# ram-2mb.net
KiCad netlist of a schematic drawn in EAGLE
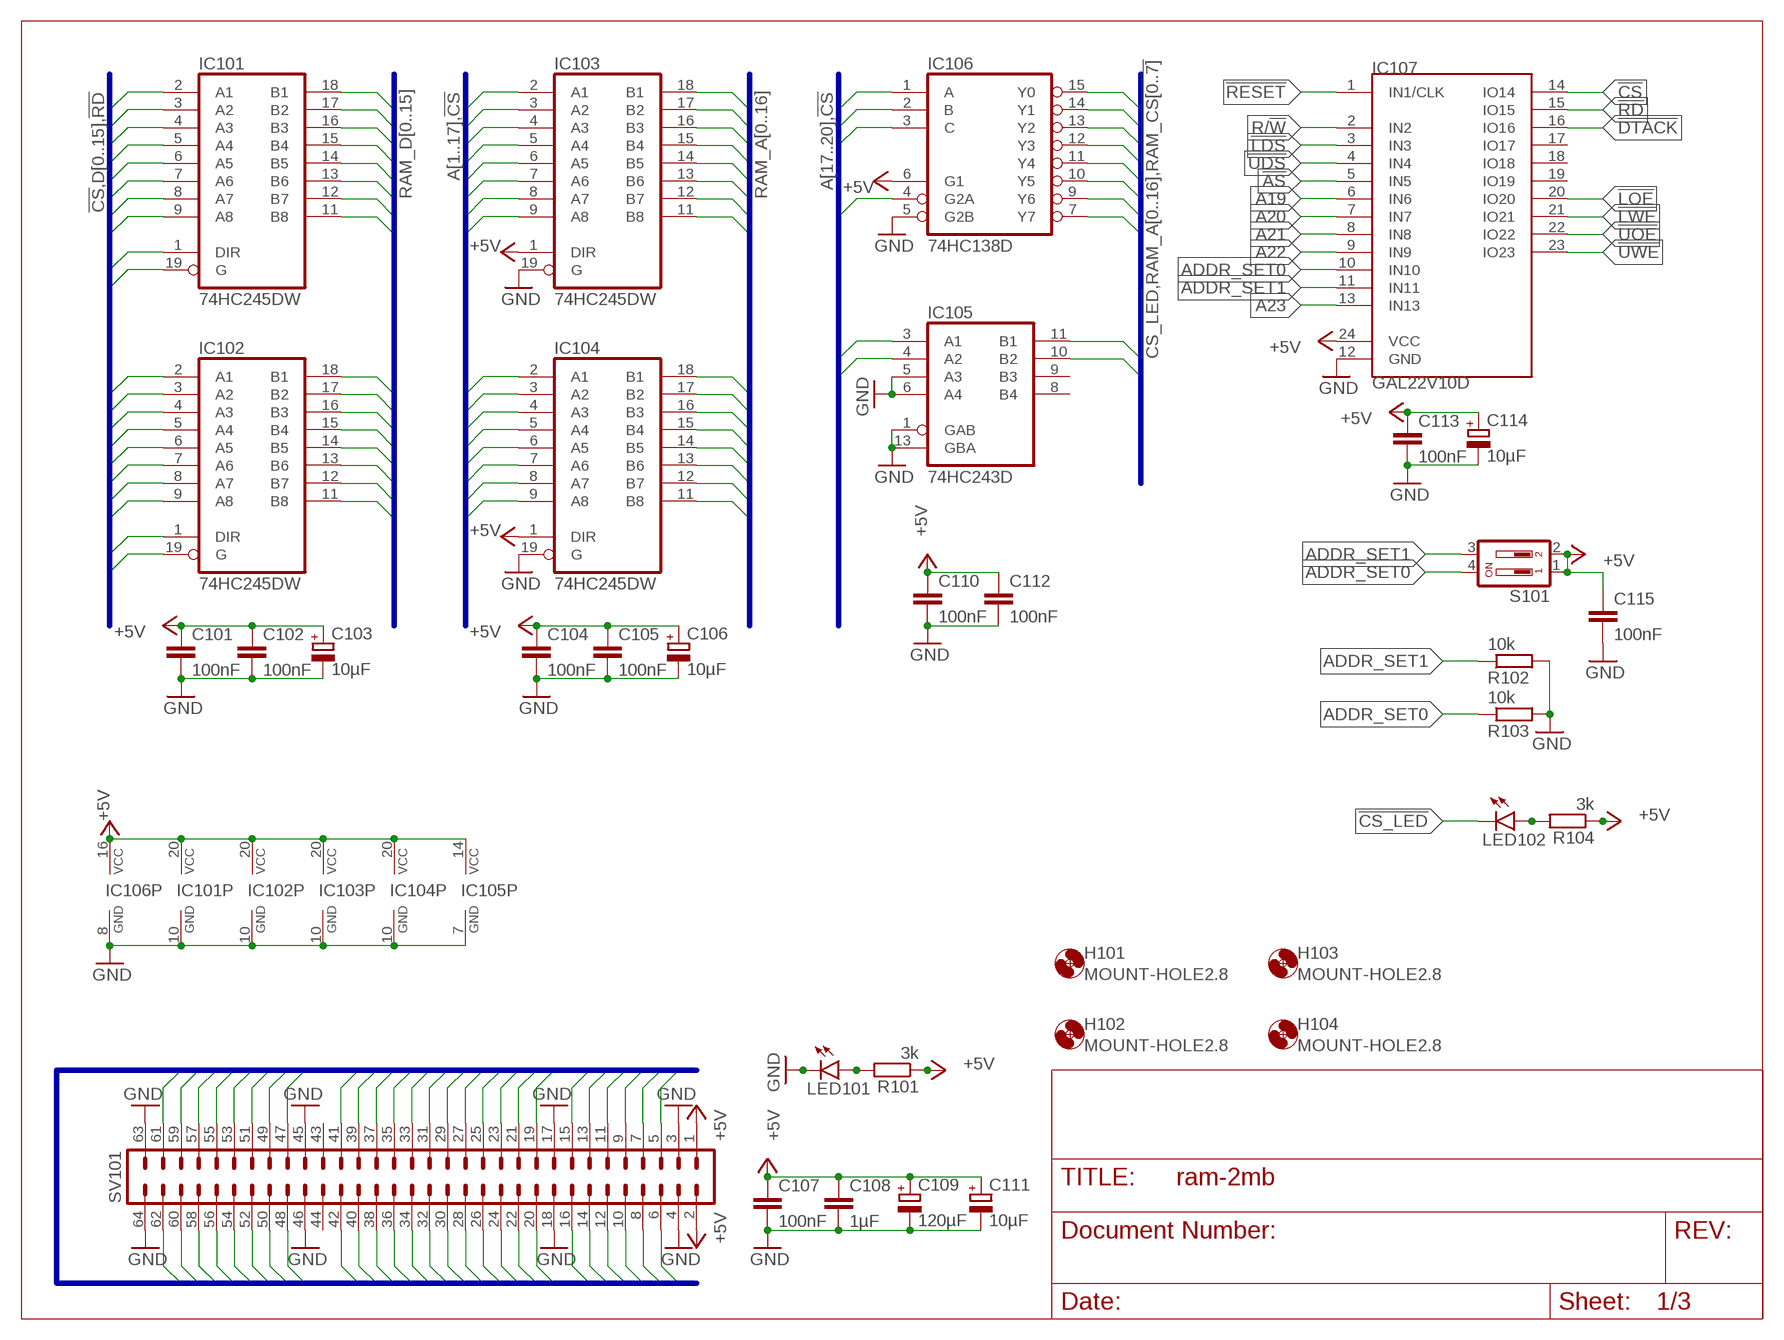
[diagram p0: schematic, sheet 1]
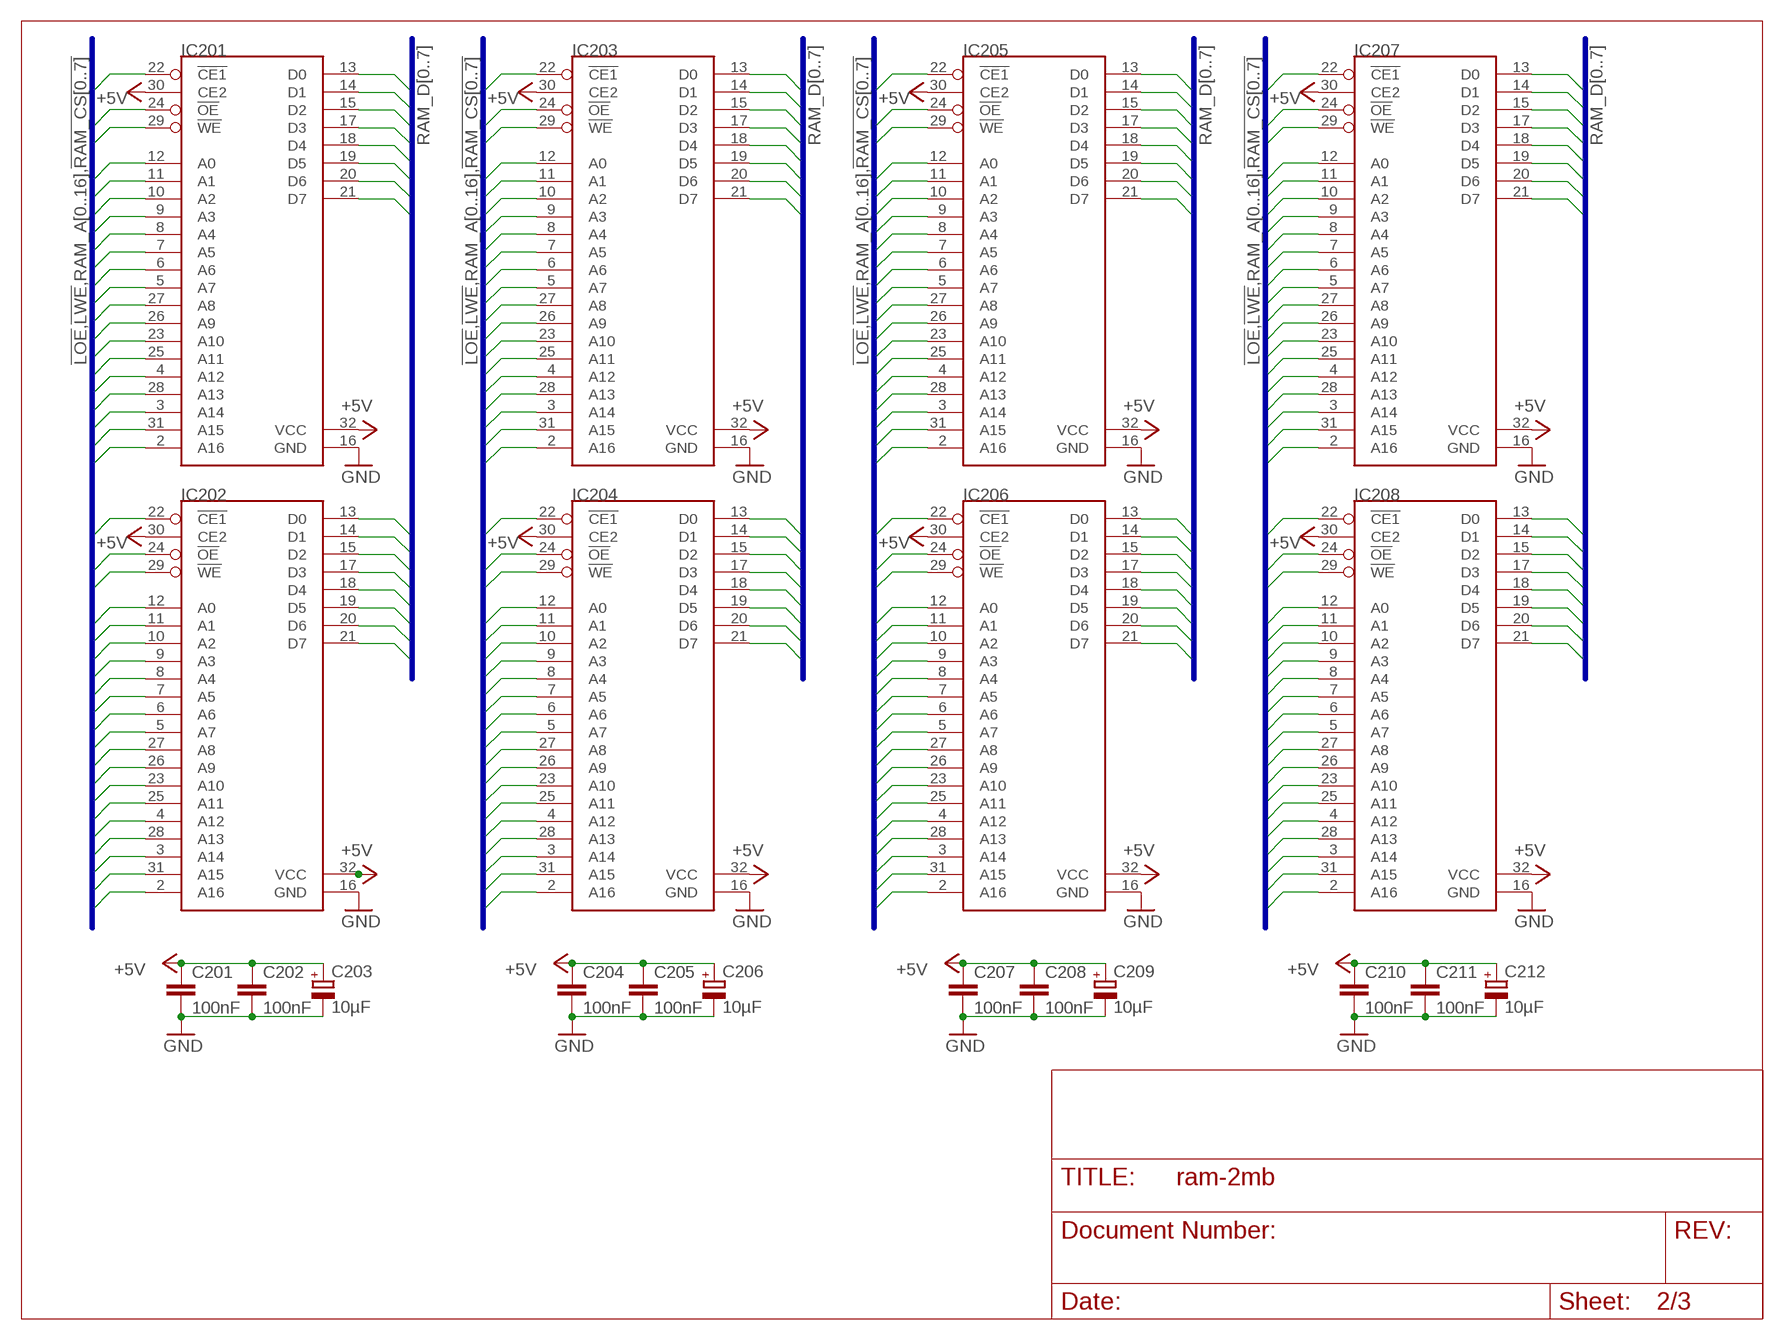
[diagram p1: schematic, sheet 2]
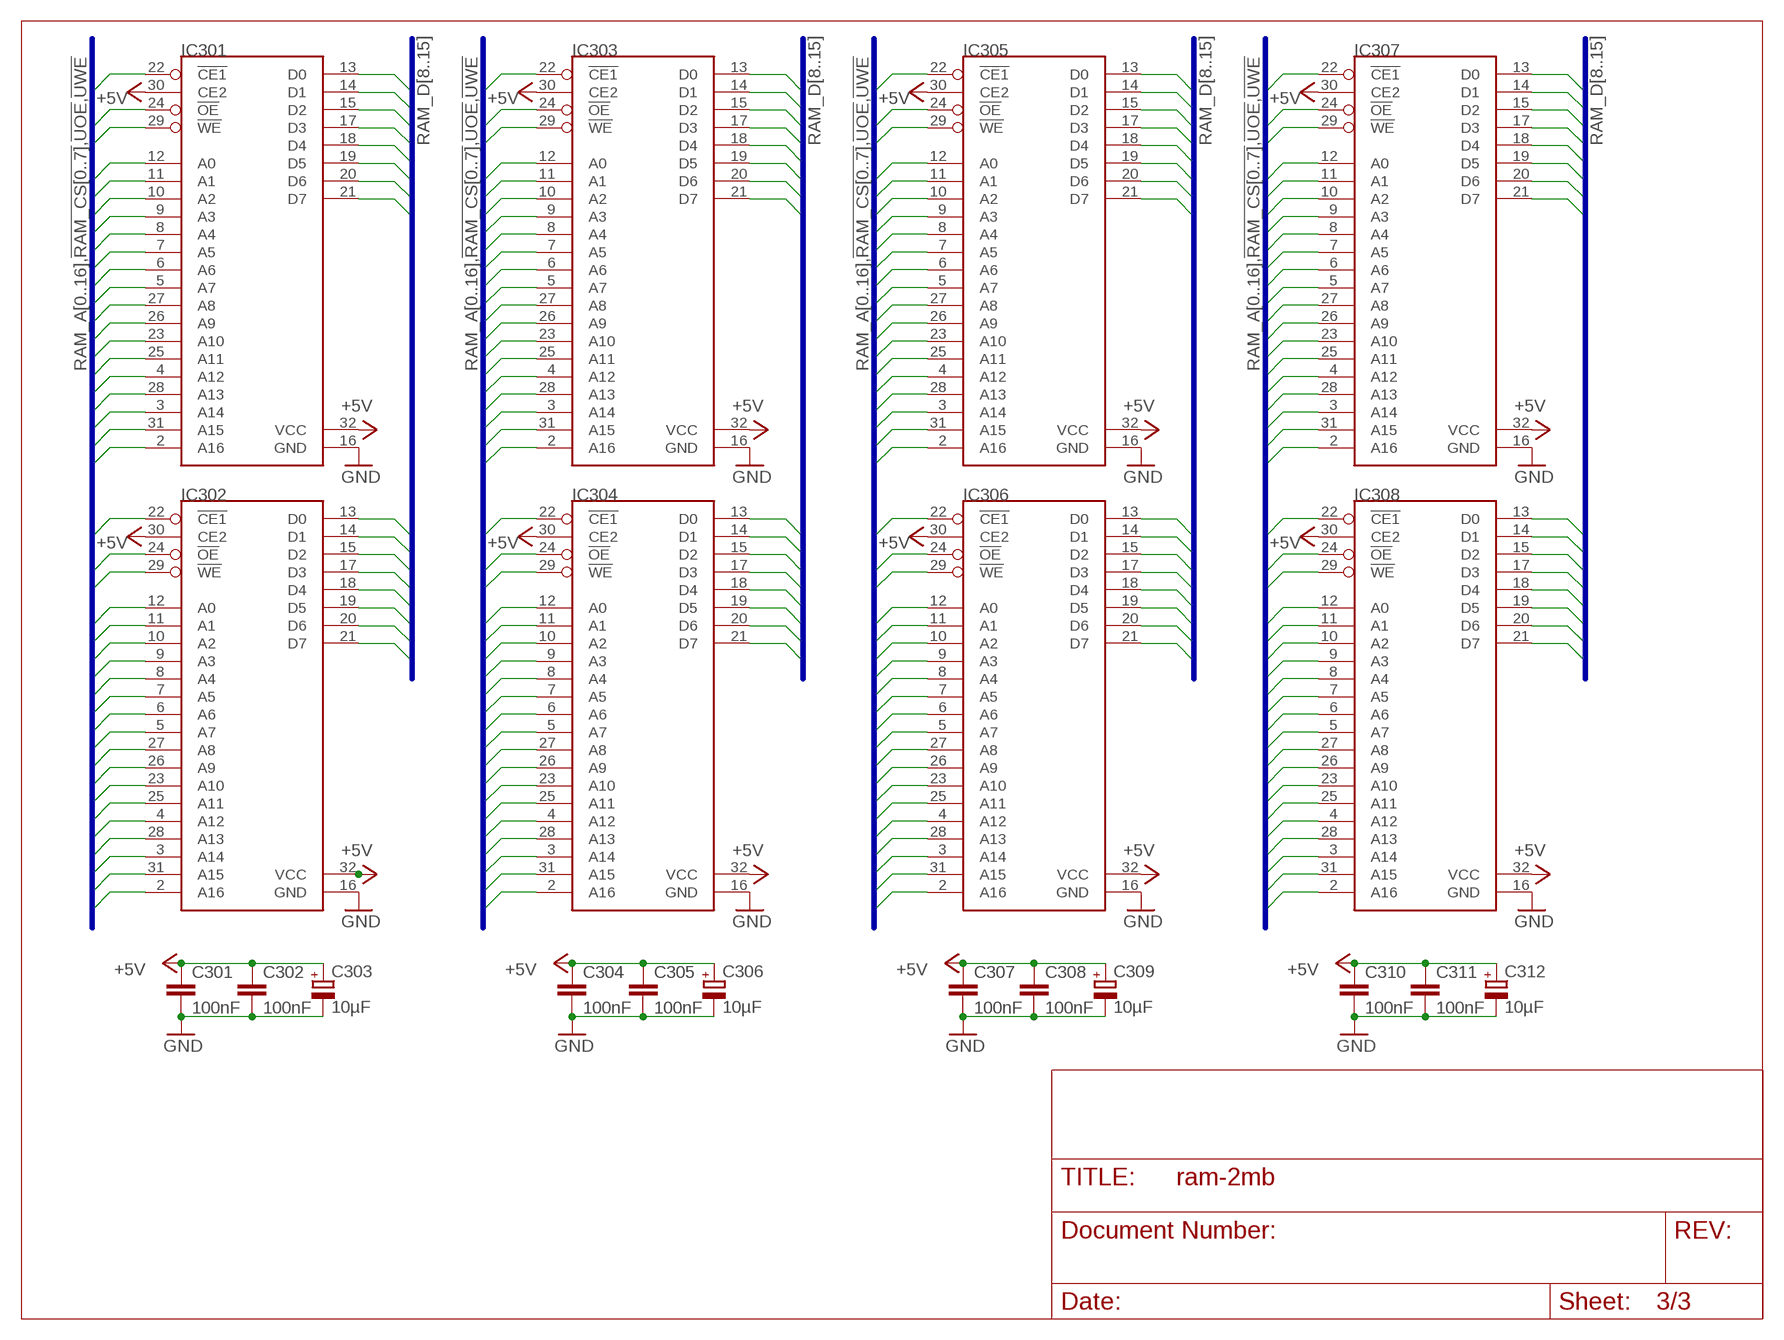
[diagram p2: schematic, sheet 3]

(export (version "E")
  (design (tool "Eeschema 10.0.6"))
  (components
    (comp (ref "C101")
      (value "100nF")
      (footprint "eagle-import:C0805")
      (libsource (lib "eagle-import") (part "C-EUC0805"))
    )
    (comp (ref "C102")
      (value "100nF")
      (footprint "eagle-import:C0805")
      (libsource (lib "eagle-import") (part "C-EUC0805"))
    )
    (comp (ref "C103")
      (value "10µF")
      (footprint "eagle-import:SMC_B")
      (libsource (lib "eagle-import") (part "CPOL-EUSMCB"))
    )
    (comp (ref "C104")
      (value "100nF")
      (footprint "eagle-import:C0805")
      (libsource (lib "eagle-import") (part "C-EUC0805"))
    )
    (comp (ref "C105")
      (value "100nF")
      (footprint "eagle-import:C0805")
      (libsource (lib "eagle-import") (part "C-EUC0805"))
    )
    (comp (ref "C106")
      (value "10µF")
      (footprint "eagle-import:SMC_B")
      (libsource (lib "eagle-import") (part "CPOL-EUSMCB"))
    )
    (comp (ref "C107")
      (value "100nF")
      (footprint "eagle-import:C0805")
      (libsource (lib "eagle-import") (part "C-EUC0805"))
    )
    (comp (ref "C108")
      (value "1µF")
      (footprint "eagle-import:C0805")
      (libsource (lib "eagle-import") (part "C-EUC0805"))
    )
    (comp (ref "C109")
      (value "120µF")
      (footprint "eagle-import:E2,5-7")
      (libsource (lib "eagle-import") (part "CPOL-EUE2.5-7"))
    )
    (comp (ref "C110")
      (value "100nF")
      (footprint "eagle-import:C0805")
      (libsource (lib "eagle-import") (part "C-EUC0805"))
    )
    (comp (ref "C111")
      (value "10µF")
      (footprint "eagle-import:SMC_B")
      (libsource (lib "eagle-import") (part "CPOL-EUSMCB"))
    )
    (comp (ref "C112")
      (value "100nF")
      (footprint "eagle-import:C0805")
      (libsource (lib "eagle-import") (part "C-EUC0805"))
    )
    (comp (ref "C113")
      (value "100nF")
      (footprint "eagle-import:C0805")
      (libsource (lib "eagle-import") (part "C-EUC0805"))
    )
    (comp (ref "C114")
      (value "10µF")
      (footprint "eagle-import:SMC_B")
      (libsource (lib "eagle-import") (part "CPOL-EUSMCB"))
    )
    (comp (ref "C115")
      (value "100nF")
      (footprint "eagle-import:C0805")
      (libsource (lib "eagle-import") (part "C-EUC0805"))
    )
    (comp (ref "H101")
      (value "MOUNT-HOLE2.8")
      (footprint "eagle-import:2,8")
      (libsource (lib "eagle-import") (part "MOUNT-HOLE2.8"))
    )
    (comp (ref "H102")
      (value "MOUNT-HOLE2.8")
      (footprint "eagle-import:2,8")
      (libsource (lib "eagle-import") (part "MOUNT-HOLE2.8"))
    )
    (comp (ref "H103")
      (value "MOUNT-HOLE2.8")
      (footprint "eagle-import:2,8")
      (libsource (lib "eagle-import") (part "MOUNT-HOLE2.8"))
    )
    (comp (ref "H104")
      (value "MOUNT-HOLE2.8")
      (footprint "eagle-import:2,8")
      (libsource (lib "eagle-import") (part "MOUNT-HOLE2.8"))
    )
    (comp (ref "IC101")
      (value "74HC245DW")
      (footprint "eagle-import:SO20W")
      (fields (field (name "MOUSER") "595-SN74HC245DWR"))
      (libsource (lib "eagle-import") (part "74245DWHC"))
    )
    (comp (ref "IC102")
      (value "74HC245DW")
      (footprint "eagle-import:SO20W")
      (fields (field (name "MOUSER") "595-SN74HC245DWR"))
      (libsource (lib "eagle-import") (part "74245DWHC"))
    )
    (comp (ref "IC103")
      (value "74HC245DW")
      (footprint "eagle-import:SO20W")
      (fields (field (name "MOUSER") "595-SN74HC245DWR"))
      (libsource (lib "eagle-import") (part "74245DWHC"))
    )
    (comp (ref "IC104")
      (value "74HC245DW")
      (footprint "eagle-import:SO20W")
      (fields (field (name "MOUSER") "595-SN74HC245DWR"))
      (libsource (lib "eagle-import") (part "74245DWHC"))
    )
    (comp (ref "IC105")
      (value "74HC243D")
      (footprint "eagle-import:SO14")
      (fields (field (name "MOUSER") "595-CD74HC243M96"))
      (libsource (lib "eagle-import") (part "74243DHC"))
    )
    (comp (ref "IC106")
      (value "74HC138D")
      (footprint "eagle-import:SO16")
      (fields (field (name "MOUSER") "595-SN74HC138DG4"))
      (libsource (lib "eagle-import") (part "74138DHC"))
    )
    (comp (ref "IC107")
      (value "GAL22V10D")
      (footprint "eagle-import:DIL24S")
      (libsource (lib "eagle-import") (part "GAL22V10DIP24"))
    )
    (comp (ref "LED101")
      (value "LEDCHIPLED_1206")
      (footprint "eagle-import:CHIPLED_1206")
      (libsource (lib "eagle-import") (part "LEDCHIPLED_1206"))
    )
    (comp (ref "LED102")
      (value "LEDCHIPLED_1206")
      (footprint "eagle-import:CHIPLED_1206")
      (libsource (lib "eagle-import") (part "LEDCHIPLED_1206"))
    )
    (comp (ref "R101")
      (value "3k")
      (footprint "eagle-import:R2012")
      (libsource (lib "eagle-import") (part "R-EU_R2012"))
    )
    (comp (ref "R102")
      (value "10k")
      (footprint "eagle-import:R2012")
      (libsource (lib "eagle-import") (part "R-EU_R2012"))
    )
    (comp (ref "R103")
      (value "10k")
      (footprint "eagle-import:R2012")
      (libsource (lib "eagle-import") (part "R-EU_R2012"))
    )
    (comp (ref "R104")
      (value "3k")
      (footprint "eagle-import:R2012")
      (libsource (lib "eagle-import") (part "R-EU_R2012"))
    )
    (comp (ref "S101")
      (value "DP02")
      (footprint "eagle-import:DP-02")
      (fields (field (name "MPN") "MCDP02"))
      (libsource (lib "eagle-import") (part "DP02"))
    )
    (comp (ref "SV101")
      (value "ML64L")
      (footprint "eagle-import:ML64L")
      (libsource (lib "eagle-import") (part "ML64L"))
    )
    (comp (ref "C301")
      (value "100nF")
      (footprint "eagle-import:C0805")
      (libsource (lib "eagle-import") (part "C-EUC0805"))
    )
    (comp (ref "C302")
      (value "100nF")
      (footprint "eagle-import:C0805")
      (libsource (lib "eagle-import") (part "C-EUC0805"))
    )
    (comp (ref "C303")
      (value "10µF")
      (footprint "eagle-import:SMC_B")
      (libsource (lib "eagle-import") (part "CPOL-EUSMCB"))
    )
    (comp (ref "C304")
      (value "100nF")
      (footprint "eagle-import:C0805")
      (libsource (lib "eagle-import") (part "C-EUC0805"))
    )
    (comp (ref "C305")
      (value "100nF")
      (footprint "eagle-import:C0805")
      (libsource (lib "eagle-import") (part "C-EUC0805"))
    )
    (comp (ref "C306")
      (value "10µF")
      (footprint "eagle-import:SMC_B")
      (libsource (lib "eagle-import") (part "CPOL-EUSMCB"))
    )
    (comp (ref "C307")
      (value "100nF")
      (footprint "eagle-import:C0805")
      (libsource (lib "eagle-import") (part "C-EUC0805"))
    )
    (comp (ref "C308")
      (value "100nF")
      (footprint "eagle-import:C0805")
      (libsource (lib "eagle-import") (part "C-EUC0805"))
    )
    (comp (ref "C309")
      (value "10µF")
      (footprint "eagle-import:SMC_B")
      (libsource (lib "eagle-import") (part "CPOL-EUSMCB"))
    )
    (comp (ref "C310")
      (value "100nF")
      (footprint "eagle-import:C0805")
      (libsource (lib "eagle-import") (part "C-EUC0805"))
    )
    (comp (ref "C311")
      (value "100nF")
      (footprint "eagle-import:C0805")
      (libsource (lib "eagle-import") (part "C-EUC0805"))
    )
    (comp (ref "C312")
      (value "10µF")
      (footprint "eagle-import:SMC_B")
      (libsource (lib "eagle-import") (part "CPOL-EUSMCB"))
    )
    (comp (ref "IC301")
      (value "CY62128BSOIC32-450")
      (footprint "eagle-import:SOIC127P1412X299-32N")
      (libsource (lib "eagle-import") (part "CY62128BSOIC32-450"))
    )
    (comp (ref "IC302")
      (value "CY62128BSOIC32-450")
      (footprint "eagle-import:SOIC127P1412X299-32N")
      (libsource (lib "eagle-import") (part "CY62128BSOIC32-450"))
    )
    (comp (ref "IC303")
      (value "CY62128BSOIC32-450")
      (footprint "eagle-import:SOIC127P1412X299-32N")
      (libsource (lib "eagle-import") (part "CY62128BSOIC32-450"))
    )
    (comp (ref "IC304")
      (value "CY62128BSOIC32-450")
      (footprint "eagle-import:SOIC127P1412X299-32N")
      (libsource (lib "eagle-import") (part "CY62128BSOIC32-450"))
    )
    (comp (ref "IC305")
      (value "CY62128BSOIC32-450")
      (footprint "eagle-import:SOIC127P1412X299-32N")
      (libsource (lib "eagle-import") (part "CY62128BSOIC32-450"))
    )
    (comp (ref "IC306")
      (value "CY62128BSOIC32-450")
      (footprint "eagle-import:SOIC127P1412X299-32N")
      (libsource (lib "eagle-import") (part "CY62128BSOIC32-450"))
    )
    (comp (ref "IC307")
      (value "CY62128BSOIC32-450")
      (footprint "eagle-import:SOIC127P1412X299-32N")
      (libsource (lib "eagle-import") (part "CY62128BSOIC32-450"))
    )
    (comp (ref "IC308")
      (value "CY62128BSOIC32-450")
      (footprint "eagle-import:SOIC127P1412X299-32N")
      (libsource (lib "eagle-import") (part "CY62128BSOIC32-450"))
    )
    (comp (ref "C201")
      (value "100nF")
      (footprint "eagle-import:C0805")
      (libsource (lib "eagle-import") (part "C-EUC0805"))
    )
    (comp (ref "C202")
      (value "100nF")
      (footprint "eagle-import:C0805")
      (libsource (lib "eagle-import") (part "C-EUC0805"))
    )
    (comp (ref "C203")
      (value "10µF")
      (footprint "eagle-import:SMC_B")
      (libsource (lib "eagle-import") (part "CPOL-EUSMCB"))
    )
    (comp (ref "C204")
      (value "100nF")
      (footprint "eagle-import:C0805")
      (libsource (lib "eagle-import") (part "C-EUC0805"))
    )
    (comp (ref "C205")
      (value "100nF")
      (footprint "eagle-import:C0805")
      (libsource (lib "eagle-import") (part "C-EUC0805"))
    )
    (comp (ref "C206")
      (value "10µF")
      (footprint "eagle-import:SMC_B")
      (libsource (lib "eagle-import") (part "CPOL-EUSMCB"))
    )
    (comp (ref "C207")
      (value "100nF")
      (footprint "eagle-import:C0805")
      (libsource (lib "eagle-import") (part "C-EUC0805"))
    )
    (comp (ref "C208")
      (value "100nF")
      (footprint "eagle-import:C0805")
      (libsource (lib "eagle-import") (part "C-EUC0805"))
    )
    (comp (ref "C209")
      (value "10µF")
      (footprint "eagle-import:SMC_B")
      (libsource (lib "eagle-import") (part "CPOL-EUSMCB"))
    )
    (comp (ref "C210")
      (value "100nF")
      (footprint "eagle-import:C0805")
      (libsource (lib "eagle-import") (part "C-EUC0805"))
    )
    (comp (ref "C211")
      (value "100nF")
      (footprint "eagle-import:C0805")
      (libsource (lib "eagle-import") (part "C-EUC0805"))
    )
    (comp (ref "C212")
      (value "10µF")
      (footprint "eagle-import:SMC_B")
      (libsource (lib "eagle-import") (part "CPOL-EUSMCB"))
    )
    (comp (ref "IC201")
      (value "CY62128BSOIC32-450")
      (footprint "eagle-import:SOIC127P1412X299-32N")
      (libsource (lib "eagle-import") (part "CY62128BSOIC32-450"))
    )
    (comp (ref "IC202")
      (value "CY62128BSOIC32-450")
      (footprint "eagle-import:SOIC127P1412X299-32N")
      (libsource (lib "eagle-import") (part "CY62128BSOIC32-450"))
    )
    (comp (ref "IC203")
      (value "CY62128BSOIC32-450")
      (footprint "eagle-import:SOIC127P1412X299-32N")
      (libsource (lib "eagle-import") (part "CY62128BSOIC32-450"))
    )
    (comp (ref "IC204")
      (value "CY62128BSOIC32-450")
      (footprint "eagle-import:SOIC127P1412X299-32N")
      (libsource (lib "eagle-import") (part "CY62128BSOIC32-450"))
    )
    (comp (ref "IC205")
      (value "CY62128BSOIC32-450")
      (footprint "eagle-import:SOIC127P1412X299-32N")
      (libsource (lib "eagle-import") (part "CY62128BSOIC32-450"))
    )
    (comp (ref "IC206")
      (value "CY62128BSOIC32-450")
      (footprint "eagle-import:SOIC127P1412X299-32N")
      (libsource (lib "eagle-import") (part "CY62128BSOIC32-450"))
    )
    (comp (ref "IC207")
      (value "CY62128BSOIC32-450")
      (footprint "eagle-import:SOIC127P1412X299-32N")
      (libsource (lib "eagle-import") (part "CY62128BSOIC32-450"))
    )
    (comp (ref "IC208")
      (value "CY62128BSOIC32-450")
      (footprint "eagle-import:SOIC127P1412X299-32N")
      (libsource (lib "eagle-import") (part "CY62128BSOIC32-450"))
    )
  )
  (nets
    (net (code "1") (name "+5V") (class "Default")
      (node (ref "C101") (pin "1") (pinfunction "1_1") (pintype "passive"))
      (node (ref "C102") (pin "1") (pinfunction "1_1") (pintype "passive"))
      (node (ref "C103") (pin "+") (pinfunction "+_+") (pintype "passive"))
      (node (ref "C104") (pin "1") (pinfunction "1_1") (pintype "passive"))
      (node (ref "C105") (pin "1") (pinfunction "1_1") (pintype "passive"))
      (node (ref "C106") (pin "+") (pinfunction "+_+") (pintype "passive"))
      (node (ref "C107") (pin "1") (pinfunction "1_1") (pintype "passive"))
      (node (ref "C108") (pin "1") (pinfunction "1_1") (pintype "passive"))
      (node (ref "C109") (pin "+") (pinfunction "+_+") (pintype "passive"))
      (node (ref "C110") (pin "1") (pinfunction "1_1") (pintype "passive"))
      (node (ref "C111") (pin "+") (pinfunction "+_+") (pintype "passive"))
      (node (ref "C112") (pin "1") (pinfunction "1_1") (pintype "passive"))
      (node (ref "C113") (pin "1") (pinfunction "1_1") (pintype "passive"))
      (node (ref "C114") (pin "+") (pinfunction "+_+") (pintype "passive"))
      (node (ref "C115") (pin "1") (pinfunction "1_1") (pintype "passive"))
      (node (ref "C201") (pin "1") (pinfunction "1_1") (pintype "passive"))
      (node (ref "C202") (pin "1") (pinfunction "1_1") (pintype "passive"))
      (node (ref "C203") (pin "+") (pinfunction "+_+") (pintype "passive"))
      (node (ref "C204") (pin "1") (pinfunction "1_1") (pintype "passive"))
      (node (ref "C205") (pin "1") (pinfunction "1_1") (pintype "passive"))
      (node (ref "C206") (pin "+") (pinfunction "+_+") (pintype "passive"))
      (node (ref "C207") (pin "1") (pinfunction "1_1") (pintype "passive"))
      (node (ref "C208") (pin "1") (pinfunction "1_1") (pintype "passive"))
      (node (ref "C209") (pin "+") (pinfunction "+_+") (pintype "passive"))
      (node (ref "C210") (pin "1") (pinfunction "1_1") (pintype "passive"))
      (node (ref "C211") (pin "1") (pinfunction "1_1") (pintype "passive"))
      (node (ref "C212") (pin "+") (pinfunction "+_+") (pintype "passive"))
      (node (ref "C301") (pin "1") (pinfunction "1_1") (pintype "passive"))
      (node (ref "C302") (pin "1") (pinfunction "1_1") (pintype "passive"))
      (node (ref "C303") (pin "+") (pinfunction "+_+") (pintype "passive"))
      (node (ref "C304") (pin "1") (pinfunction "1_1") (pintype "passive"))
      (node (ref "C305") (pin "1") (pinfunction "1_1") (pintype "passive"))
      (node (ref "C306") (pin "+") (pinfunction "+_+") (pintype "passive"))
      (node (ref "C307") (pin "1") (pinfunction "1_1") (pintype "passive"))
      (node (ref "C308") (pin "1") (pinfunction "1_1") (pintype "passive"))
      (node (ref "C309") (pin "+") (pinfunction "+_+") (pintype "passive"))
      (node (ref "C310") (pin "1") (pinfunction "1_1") (pintype "passive"))
      (node (ref "C311") (pin "1") (pinfunction "1_1") (pintype "passive"))
      (node (ref "C312") (pin "+") (pinfunction "+_+") (pintype "passive"))
      (node (ref "IC101") (pin "20") (pinfunction "VCC_20") (pintype "power_in"))
      (node (ref "IC102") (pin "20") (pinfunction "VCC_20") (pintype "power_in"))
      (node (ref "IC103") (pin "1") (pinfunction "DIR_1") (pintype "input"))
      (node (ref "IC103") (pin "20") (pinfunction "VCC_20") (pintype "power_in"))
      (node (ref "IC104") (pin "1") (pinfunction "DIR_1") (pintype "input"))
      (node (ref "IC104") (pin "20") (pinfunction "VCC_20") (pintype "power_in"))
      (node (ref "IC105") (pin "14") (pinfunction "VCC_14") (pintype "power_in"))
      (node (ref "IC106") (pin "16") (pinfunction "VCC_16") (pintype "power_in"))
      (node (ref "IC106") (pin "6") (pinfunction "G1_6") (pintype "input"))
      (node (ref "IC107") (pin "24") (pinfunction "VCC_24") (pintype "power_in"))
      (node (ref "IC201") (pin "30") (pinfunction "CE2_30") (pintype "input"))
      (node (ref "IC201") (pin "32") (pinfunction "VCC_32") (pintype "power_in"))
      (node (ref "IC202") (pin "30") (pinfunction "CE2_30") (pintype "input"))
      (node (ref "IC202") (pin "32") (pinfunction "VCC_32") (pintype "power_in"))
      (node (ref "IC203") (pin "30") (pinfunction "CE2_30") (pintype "input"))
      (node (ref "IC203") (pin "32") (pinfunction "VCC_32") (pintype "power_in"))
      (node (ref "IC204") (pin "30") (pinfunction "CE2_30") (pintype "input"))
      (node (ref "IC204") (pin "32") (pinfunction "VCC_32") (pintype "power_in"))
      (node (ref "IC205") (pin "30") (pinfunction "CE2_30") (pintype "input"))
      (node (ref "IC205") (pin "32") (pinfunction "VCC_32") (pintype "power_in"))
      (node (ref "IC206") (pin "30") (pinfunction "CE2_30") (pintype "input"))
      (node (ref "IC206") (pin "32") (pinfunction "VCC_32") (pintype "power_in"))
      (node (ref "IC207") (pin "30") (pinfunction "CE2_30") (pintype "input"))
      (node (ref "IC207") (pin "32") (pinfunction "VCC_32") (pintype "power_in"))
      (node (ref "IC208") (pin "30") (pinfunction "CE2_30") (pintype "input"))
      (node (ref "IC208") (pin "32") (pinfunction "VCC_32") (pintype "power_in"))
      (node (ref "IC301") (pin "30") (pinfunction "CE2_30") (pintype "input"))
      (node (ref "IC301") (pin "32") (pinfunction "VCC_32") (pintype "power_in"))
      (node (ref "IC302") (pin "30") (pinfunction "CE2_30") (pintype "input"))
      (node (ref "IC302") (pin "32") (pinfunction "VCC_32") (pintype "power_in"))
      (node (ref "IC303") (pin "30") (pinfunction "CE2_30") (pintype "input"))
      (node (ref "IC303") (pin "32") (pinfunction "VCC_32") (pintype "power_in"))
      (node (ref "IC304") (pin "30") (pinfunction "CE2_30") (pintype "input"))
      (node (ref "IC304") (pin "32") (pinfunction "VCC_32") (pintype "power_in"))
      (node (ref "IC305") (pin "30") (pinfunction "CE2_30") (pintype "input"))
      (node (ref "IC305") (pin "32") (pinfunction "VCC_32") (pintype "power_in"))
      (node (ref "IC306") (pin "30") (pinfunction "CE2_30") (pintype "input"))
      (node (ref "IC306") (pin "32") (pinfunction "VCC_32") (pintype "power_in"))
      (node (ref "IC307") (pin "30") (pinfunction "CE2_30") (pintype "input"))
      (node (ref "IC307") (pin "32") (pinfunction "VCC_32") (pintype "power_in"))
      (node (ref "IC308") (pin "30") (pinfunction "CE2_30") (pintype "input"))
      (node (ref "IC308") (pin "32") (pinfunction "VCC_32") (pintype "power_in"))
      (node (ref "R101") (pin "1") (pinfunction "1_1") (pintype "passive"))
      (node (ref "R104") (pin "1") (pinfunction "1_1") (pintype "passive"))
      (node (ref "S101") (pin "1") (pinfunction "1_1") (pintype "passive"))
      (node (ref "S101") (pin "2") (pinfunction "2_2") (pintype "passive"))
      (node (ref "SV101") (pin "1") (pinfunction "1_1") (pintype "passive"))
      (node (ref "SV101") (pin "2") (pinfunction "2_2") (pintype "passive"))
    )
    (net (code "12") (name "A1") (class "Default")
      (node (ref "IC103") (pin "2") (pinfunction "A1_2") (pintype "bidirectional"))
      (node (ref "SV101") (pin "20") (pinfunction "20_20") (pintype "passive"))
    )
    (net (code "13") (name "A2") (class "Default")
      (node (ref "IC103") (pin "3") (pinfunction "A2_3") (pintype "bidirectional"))
      (node (ref "SV101") (pin "22") (pinfunction "22_22") (pintype "passive"))
    )
    (net (code "14") (name "A3") (class "Default")
      (node (ref "IC103") (pin "4") (pinfunction "A3_4") (pintype "bidirectional"))
      (node (ref "SV101") (pin "19") (pinfunction "19_19") (pintype "passive"))
    )
    (net (code "15") (name "A4") (class "Default")
      (node (ref "IC103") (pin "5") (pinfunction "A4_5") (pintype "bidirectional"))
      (node (ref "SV101") (pin "24") (pinfunction "24_24") (pintype "passive"))
    )
    (net (code "16") (name "A5") (class "Default")
      (node (ref "IC103") (pin "6") (pinfunction "A5_6") (pintype "bidirectional"))
      (node (ref "SV101") (pin "21") (pinfunction "21_21") (pintype "passive"))
    )
    (net (code "17") (name "A6") (class "Default")
      (node (ref "IC103") (pin "7") (pinfunction "A6_7") (pintype "bidirectional"))
      (node (ref "SV101") (pin "23") (pinfunction "23_23") (pintype "passive"))
    )
    (net (code "18") (name "A7") (class "Default")
      (node (ref "IC103") (pin "8") (pinfunction "A7_8") (pintype "bidirectional"))
      (node (ref "SV101") (pin "26") (pinfunction "26_26") (pintype "passive"))
    )
    (net (code "19") (name "A8") (class "Default")
      (node (ref "IC103") (pin "9") (pinfunction "A8_9") (pintype "bidirectional"))
      (node (ref "SV101") (pin "25") (pinfunction "25_25") (pintype "passive"))
    )
    (net (code "20") (name "A9") (class "Default")
      (node (ref "IC104") (pin "2") (pinfunction "A1_2") (pintype "bidirectional"))
      (node (ref "SV101") (pin "28") (pinfunction "28_28") (pintype "passive"))
    )
    (net (code "21") (name "A10") (class "Default")
      (node (ref "IC104") (pin "3") (pinfunction "A2_3") (pintype "bidirectional"))
      (node (ref "SV101") (pin "27") (pinfunction "27_27") (pintype "passive"))
    )
    (net (code "22") (name "A11") (class "Default")
      (node (ref "IC104") (pin "4") (pinfunction "A3_4") (pintype "bidirectional"))
      (node (ref "SV101") (pin "30") (pinfunction "30_30") (pintype "passive"))
    )
    (net (code "23") (name "A12") (class "Default")
      (node (ref "IC104") (pin "5") (pinfunction "A4_5") (pintype "bidirectional"))
      (node (ref "SV101") (pin "29") (pinfunction "29_29") (pintype "passive"))
    )
    (net (code "24") (name "A13") (class "Default")
      (node (ref "IC104") (pin "6") (pinfunction "A5_6") (pintype "bidirectional"))
      (node (ref "SV101") (pin "31") (pinfunction "31_31") (pintype "passive"))
    )
    (net (code "25") (name "A14") (class "Default")
      (node (ref "IC104") (pin "7") (pinfunction "A6_7") (pintype "bidirectional"))
      (node (ref "SV101") (pin "32") (pinfunction "32_32") (pintype "passive"))
    )
    (net (code "26") (name "A15") (class "Default")
      (node (ref "IC104") (pin "8") (pinfunction "A7_8") (pintype "bidirectional"))
      (node (ref "SV101") (pin "33") (pinfunction "33_33") (pintype "passive"))
    )
    (net (code "27") (name "A16") (class "Default")
      (node (ref "IC104") (pin "9") (pinfunction "A8_9") (pintype "bidirectional"))
      (node (ref "SV101") (pin "34") (pinfunction "34_34") (pintype "passive"))
    )
    (net (code "28") (name "A17") (class "Default")
      (node (ref "IC105") (pin "3") (pinfunction "A1_3") (pintype "bidirectional"))
      (node (ref "SV101") (pin "36") (pinfunction "36_36") (pintype "passive"))
    )
    (net (code "29") (name "A18") (class "Default")
      (node (ref "IC106") (pin "1") (pinfunction "A_1") (pintype "input"))
      (node (ref "SV101") (pin "35") (pinfunction "35_35") (pintype "passive"))
    )
    (net (code "30") (name "A19") (class "Default")
      (node (ref "IC106") (pin "2") (pinfunction "B_2") (pintype "input"))
      (node (ref "IC107") (pin "6") (pinfunction "IN6_6") (pintype "input"))
      (node (ref "SV101") (pin "38") (pinfunction "38_38") (pintype "passive"))
    )
    (net (code "31") (name "A20") (class "Default")
      (node (ref "IC106") (pin "3") (pinfunction "C_3") (pintype "input"))
      (node (ref "IC107") (pin "7") (pinfunction "IN7_7") (pintype "input"))
      (node (ref "SV101") (pin "37") (pinfunction "37_37") (pintype "passive"))
    )
    (net (code "32") (name "A21") (class "Default")
      (node (ref "IC107") (pin "8") (pinfunction "IN8_8") (pintype "input"))
      (node (ref "SV101") (pin "40") (pinfunction "40_40") (pintype "passive"))
    )
    (net (code "33") (name "A22") (class "Default")
      (node (ref "IC107") (pin "9") (pinfunction "IN9_9") (pintype "input"))
      (node (ref "SV101") (pin "39") (pinfunction "39_39") (pintype "passive"))
    )
    (net (code "34") (name "A23") (class "Default")
      (node (ref "IC107") (pin "13") (pinfunction "IN13_13") (pintype "input"))
      (node (ref "SV101") (pin "42") (pinfunction "42_42") (pintype "passive"))
    )
    (net (code "35") (name "ADDR_SET0") (class "Default")
      (node (ref "IC107") (pin "10") (pinfunction "IN10_10") (pintype "input"))
      (node (ref "R103") (pin "1") (pinfunction "1_1") (pintype "passive"))
      (node (ref "S101") (pin "4") (pinfunction "4_4") (pintype "passive"))
    )
    (net (code "36") (name "ADDR_SET1") (class "Default")
      (node (ref "IC107") (pin "11") (pinfunction "IN11_11") (pintype "input"))
      (node (ref "R102") (pin "1") (pinfunction "1_1") (pintype "passive"))
      (node (ref "S101") (pin "3") (pinfunction "3_3") (pintype "passive"))
    )
    (net (code "37") (name "D0") (class "Default")
      (node (ref "IC101") (pin "2") (pinfunction "A1_2") (pintype "bidirectional"))
      (node (ref "SV101") (pin "62") (pinfunction "62_62") (pintype "passive"))
    )
    (net (code "38") (name "D1") (class "Default")
      (node (ref "IC101") (pin "3") (pinfunction "A2_3") (pintype "bidirectional"))
      (node (ref "SV101") (pin "60") (pinfunction "60_60") (pintype "passive"))
    )
    (net (code "39") (name "D2") (class "Default")
      (node (ref "IC101") (pin "4") (pinfunction "A3_4") (pintype "bidirectional"))
      (node (ref "SV101") (pin "58") (pinfunction "58_58") (pintype "passive"))
    )
    (net (code "40") (name "D3") (class "Default")
      (node (ref "IC101") (pin "5") (pinfunction "A4_5") (pintype "bidirectional"))
      (node (ref "SV101") (pin "56") (pinfunction "56_56") (pintype "passive"))
    )
    (net (code "41") (name "D4") (class "Default")
      (node (ref "IC101") (pin "6") (pinfunction "A5_6") (pintype "bidirectional"))
      (node (ref "SV101") (pin "54") (pinfunction "54_54") (pintype "passive"))
    )
    (net (code "42") (name "D5") (class "Default")
      (node (ref "IC101") (pin "7") (pinfunction "A6_7") (pintype "bidirectional"))
      (node (ref "SV101") (pin "52") (pinfunction "52_52") (pintype "passive"))
    )
    (net (code "43") (name "D6") (class "Default")
      (node (ref "IC101") (pin "8") (pinfunction "A7_8") (pintype "bidirectional"))
      (node (ref "SV101") (pin "50") (pinfunction "50_50") (pintype "passive"))
    )
    (net (code "44") (name "D7") (class "Default")
      (node (ref "IC101") (pin "9") (pinfunction "A8_9") (pintype "bidirectional"))
      (node (ref "SV101") (pin "48") (pinfunction "48_48") (pintype "passive"))
    )
    (net (code "45") (name "D8") (class "Default")
      (node (ref "IC102") (pin "2") (pinfunction "A1_2") (pintype "bidirectional"))
      (node (ref "SV101") (pin "57") (pinfunction "57_57") (pintype "passive"))
    )
    (net (code "46") (name "D9") (class "Default")
      (node (ref "IC102") (pin "3") (pinfunction "A2_3") (pintype "bidirectional"))
      (node (ref "SV101") (pin "59") (pinfunction "59_59") (pintype "passive"))
    )
    (net (code "47") (name "D10") (class "Default")
      (node (ref "IC102") (pin "4") (pinfunction "A3_4") (pintype "bidirectional"))
      (node (ref "SV101") (pin "61") (pinfunction "61_61") (pintype "passive"))
    )
    (net (code "48") (name "D11") (class "Default")
      (node (ref "IC102") (pin "5") (pinfunction "A4_5") (pintype "bidirectional"))
      (node (ref "SV101") (pin "55") (pinfunction "55_55") (pintype "passive"))
    )
    (net (code "49") (name "D12") (class "Default")
      (node (ref "IC102") (pin "6") (pinfunction "A5_6") (pintype "bidirectional"))
      (node (ref "SV101") (pin "53") (pinfunction "53_53") (pintype "passive"))
    )
    (net (code "50") (name "D13") (class "Default")
      (node (ref "IC102") (pin "7") (pinfunction "A6_7") (pintype "bidirectional"))
      (node (ref "SV101") (pin "51") (pinfunction "51_51") (pintype "passive"))
    )
    (net (code "51") (name "D14") (class "Default")
      (node (ref "IC102") (pin "8") (pinfunction "A7_8") (pintype "bidirectional"))
      (node (ref "SV101") (pin "49") (pinfunction "49_49") (pintype "passive"))
    )
    (net (code "52") (name "D15") (class "Default")
      (node (ref "IC102") (pin "9") (pinfunction "A8_9") (pintype "bidirectional"))
      (node (ref "SV101") (pin "47") (pinfunction "47_47") (pintype "passive"))
    )
    (net (code "53") (name "GND") (class "Default")
      (node (ref "C101") (pin "2") (pinfunction "2_2") (pintype "passive"))
      (node (ref "C102") (pin "2") (pinfunction "2_2") (pintype "passive"))
      (node (ref "C103") (pin "-") (pinfunction "-_-") (pintype "passive"))
      (node (ref "C104") (pin "2") (pinfunction "2_2") (pintype "passive"))
      (node (ref "C105") (pin "2") (pinfunction "2_2") (pintype "passive"))
      (node (ref "C106") (pin "-") (pinfunction "-_-") (pintype "passive"))
      (node (ref "C107") (pin "2") (pinfunction "2_2") (pintype "passive"))
      (node (ref "C108") (pin "2") (pinfunction "2_2") (pintype "passive"))
      (node (ref "C109") (pin "-") (pinfunction "-_-") (pintype "passive"))
      (node (ref "C110") (pin "2") (pinfunction "2_2") (pintype "passive"))
      (node (ref "C111") (pin "-") (pinfunction "-_-") (pintype "passive"))
      (node (ref "C112") (pin "2") (pinfunction "2_2") (pintype "passive"))
      (node (ref "C113") (pin "2") (pinfunction "2_2") (pintype "passive"))
      (node (ref "C114") (pin "-") (pinfunction "-_-") (pintype "passive"))
      (node (ref "C115") (pin "2") (pinfunction "2_2") (pintype "passive"))
      (node (ref "C201") (pin "2") (pinfunction "2_2") (pintype "passive"))
      (node (ref "C202") (pin "2") (pinfunction "2_2") (pintype "passive"))
      (node (ref "C203") (pin "-") (pinfunction "-_-") (pintype "passive"))
      (node (ref "C204") (pin "2") (pinfunction "2_2") (pintype "passive"))
      (node (ref "C205") (pin "2") (pinfunction "2_2") (pintype "passive"))
      (node (ref "C206") (pin "-") (pinfunction "-_-") (pintype "passive"))
      (node (ref "C207") (pin "2") (pinfunction "2_2") (pintype "passive"))
      (node (ref "C208") (pin "2") (pinfunction "2_2") (pintype "passive"))
      (node (ref "C209") (pin "-") (pinfunction "-_-") (pintype "passive"))
      (node (ref "C210") (pin "2") (pinfunction "2_2") (pintype "passive"))
      (node (ref "C211") (pin "2") (pinfunction "2_2") (pintype "passive"))
      (node (ref "C212") (pin "-") (pinfunction "-_-") (pintype "passive"))
      (node (ref "C301") (pin "2") (pinfunction "2_2") (pintype "passive"))
      (node (ref "C302") (pin "2") (pinfunction "2_2") (pintype "passive"))
      (node (ref "C303") (pin "-") (pinfunction "-_-") (pintype "passive"))
      (node (ref "C304") (pin "2") (pinfunction "2_2") (pintype "passive"))
      (node (ref "C305") (pin "2") (pinfunction "2_2") (pintype "passive"))
      (node (ref "C306") (pin "-") (pinfunction "-_-") (pintype "passive"))
      (node (ref "C307") (pin "2") (pinfunction "2_2") (pintype "passive"))
      (node (ref "C308") (pin "2") (pinfunction "2_2") (pintype "passive"))
      (node (ref "C309") (pin "-") (pinfunction "-_-") (pintype "passive"))
      (node (ref "C310") (pin "2") (pinfunction "2_2") (pintype "passive"))
      (node (ref "C311") (pin "2") (pinfunction "2_2") (pintype "passive"))
      (node (ref "C312") (pin "-") (pinfunction "-_-") (pintype "passive"))
      (node (ref "IC101") (pin "10") (pinfunction "GND_10") (pintype "power_in"))
      (node (ref "IC102") (pin "10") (pinfunction "GND_10") (pintype "power_in"))
      (node (ref "IC103") (pin "10") (pinfunction "GND_10") (pintype "power_in"))
      (node (ref "IC103") (pin "19") (pinfunction "G_19") (pintype "input"))
      (node (ref "IC104") (pin "10") (pinfunction "GND_10") (pintype "power_in"))
      (node (ref "IC104") (pin "19") (pinfunction "G_19") (pintype "input"))
      (node (ref "IC105") (pin "1") (pinfunction "GAB_1") (pintype "input"))
      (node (ref "IC105") (pin "13") (pinfunction "GBA_13") (pintype "input"))
      (node (ref "IC105") (pin "5") (pinfunction "A3_5") (pintype "bidirectional"))
      (node (ref "IC105") (pin "6") (pinfunction "A4_6") (pintype "bidirectional"))
      (node (ref "IC105") (pin "7") (pinfunction "GND_7") (pintype "power_in"))
      (node (ref "IC106") (pin "5") (pinfunction "G2B_5") (pintype "input"))
      (node (ref "IC106") (pin "8") (pinfunction "GND_8") (pintype "power_in"))
      (node (ref "IC107") (pin "12") (pinfunction "GND_12") (pintype "power_in"))
      (node (ref "IC201") (pin "16") (pinfunction "GND_16") (pintype "power_in"))
      (node (ref "IC202") (pin "16") (pinfunction "GND_16") (pintype "power_in"))
      (node (ref "IC203") (pin "16") (pinfunction "GND_16") (pintype "power_in"))
      (node (ref "IC204") (pin "16") (pinfunction "GND_16") (pintype "power_in"))
      (node (ref "IC205") (pin "16") (pinfunction "GND_16") (pintype "power_in"))
      (node (ref "IC206") (pin "16") (pinfunction "GND_16") (pintype "power_in"))
      (node (ref "IC207") (pin "16") (pinfunction "GND_16") (pintype "power_in"))
      (node (ref "IC208") (pin "16") (pinfunction "GND_16") (pintype "power_in"))
      (node (ref "IC301") (pin "16") (pinfunction "GND_16") (pintype "power_in"))
      (node (ref "IC302") (pin "16") (pinfunction "GND_16") (pintype "power_in"))
      (node (ref "IC303") (pin "16") (pinfunction "GND_16") (pintype "power_in"))
      (node (ref "IC304") (pin "16") (pinfunction "GND_16") (pintype "power_in"))
      (node (ref "IC305") (pin "16") (pinfunction "GND_16") (pintype "power_in"))
      (node (ref "IC306") (pin "16") (pinfunction "GND_16") (pintype "power_in"))
      (node (ref "IC307") (pin "16") (pinfunction "GND_16") (pintype "power_in"))
      (node (ref "IC308") (pin "16") (pinfunction "GND_16") (pintype "power_in"))
      (node (ref "LED101") (pin "C") (pinfunction "C_C") (pintype "passive"))
      (node (ref "R102") (pin "2") (pinfunction "2_2") (pintype "passive"))
      (node (ref "R103") (pin "2") (pinfunction "2_2") (pintype "passive"))
      (node (ref "SV101") (pin "17") (pinfunction "17_17") (pintype "passive"))
      (node (ref "SV101") (pin "18") (pinfunction "18_18") (pintype "passive"))
      (node (ref "SV101") (pin "3") (pinfunction "3_3") (pintype "passive"))
      (node (ref "SV101") (pin "4") (pinfunction "4_4") (pintype "passive"))
      (node (ref "SV101") (pin "45") (pinfunction "45_45") (pintype "passive"))
      (node (ref "SV101") (pin "46") (pinfunction "46_46") (pintype "passive"))
      (node (ref "SV101") (pin "63") (pinfunction "63_63") (pintype "passive"))
      (node (ref "SV101") (pin "64") (pinfunction "64_64") (pintype "passive"))
    )
    (net (code "54") (name "Net-(LED101-PadA)") (class "Default")
      (node (ref "LED101") (pin "A") (pinfunction "A_A") (pintype "passive"))
      (node (ref "R101") (pin "2") (pinfunction "2_2") (pintype "passive"))
    )
    (net (code "55") (name "Net-(LED102-PadA)") (class "Default")
      (node (ref "LED102") (pin "A") (pinfunction "A_A") (pintype "passive"))
      (node (ref "R104") (pin "2") (pinfunction "2_2") (pintype "passive"))
    )
    (net (code "56") (name "RAM_A0") (class "Default")
      (node (ref "IC103") (pin "18") (pinfunction "B1_18") (pintype "bidirectional"))
      (node (ref "IC201") (pin "12") (pinfunction "A0_12") (pintype "input"))
      (node (ref "IC202") (pin "12") (pinfunction "A0_12") (pintype "input"))
      (node (ref "IC203") (pin "12") (pinfunction "A0_12") (pintype "input"))
      (node (ref "IC204") (pin "12") (pinfunction "A0_12") (pintype "input"))
      (node (ref "IC205") (pin "12") (pinfunction "A0_12") (pintype "input"))
      (node (ref "IC206") (pin "12") (pinfunction "A0_12") (pintype "input"))
      (node (ref "IC207") (pin "12") (pinfunction "A0_12") (pintype "input"))
      (node (ref "IC208") (pin "12") (pinfunction "A0_12") (pintype "input"))
      (node (ref "IC301") (pin "12") (pinfunction "A0_12") (pintype "input"))
      (node (ref "IC302") (pin "12") (pinfunction "A0_12") (pintype "input"))
      (node (ref "IC303") (pin "12") (pinfunction "A0_12") (pintype "input"))
      (node (ref "IC304") (pin "12") (pinfunction "A0_12") (pintype "input"))
      (node (ref "IC305") (pin "12") (pinfunction "A0_12") (pintype "input"))
      (node (ref "IC306") (pin "12") (pinfunction "A0_12") (pintype "input"))
      (node (ref "IC307") (pin "12") (pinfunction "A0_12") (pintype "input"))
      (node (ref "IC308") (pin "12") (pinfunction "A0_12") (pintype "input"))
    )
    (net (code "57") (name "RAM_A1") (class "Default")
      (node (ref "IC103") (pin "17") (pinfunction "B2_17") (pintype "bidirectional"))
      (node (ref "IC201") (pin "11") (pinfunction "A1_11") (pintype "input"))
      (node (ref "IC202") (pin "11") (pinfunction "A1_11") (pintype "input"))
      (node (ref "IC203") (pin "11") (pinfunction "A1_11") (pintype "input"))
      (node (ref "IC204") (pin "11") (pinfunction "A1_11") (pintype "input"))
      (node (ref "IC205") (pin "11") (pinfunction "A1_11") (pintype "input"))
      (node (ref "IC206") (pin "11") (pinfunction "A1_11") (pintype "input"))
      (node (ref "IC207") (pin "11") (pinfunction "A1_11") (pintype "input"))
      (node (ref "IC208") (pin "11") (pinfunction "A1_11") (pintype "input"))
      (node (ref "IC301") (pin "11") (pinfunction "A1_11") (pintype "input"))
      (node (ref "IC302") (pin "11") (pinfunction "A1_11") (pintype "input"))
      (node (ref "IC303") (pin "11") (pinfunction "A1_11") (pintype "input"))
      (node (ref "IC304") (pin "11") (pinfunction "A1_11") (pintype "input"))
      (node (ref "IC305") (pin "11") (pinfunction "A1_11") (pintype "input"))
      (node (ref "IC306") (pin "11") (pinfunction "A1_11") (pintype "input"))
      (node (ref "IC307") (pin "11") (pinfunction "A1_11") (pintype "input"))
      (node (ref "IC308") (pin "11") (pinfunction "A1_11") (pintype "input"))
    )
    (net (code "58") (name "RAM_A2") (class "Default")
      (node (ref "IC103") (pin "16") (pinfunction "B3_16") (pintype "bidirectional"))
      (node (ref "IC201") (pin "10") (pinfunction "A2_10") (pintype "input"))
      (node (ref "IC202") (pin "10") (pinfunction "A2_10") (pintype "input"))
      (node (ref "IC203") (pin "10") (pinfunction "A2_10") (pintype "input"))
      (node (ref "IC204") (pin "10") (pinfunction "A2_10") (pintype "input"))
      (node (ref "IC205") (pin "10") (pinfunction "A2_10") (pintype "input"))
      (node (ref "IC206") (pin "10") (pinfunction "A2_10") (pintype "input"))
      (node (ref "IC207") (pin "10") (pinfunction "A2_10") (pintype "input"))
      (node (ref "IC208") (pin "10") (pinfunction "A2_10") (pintype "input"))
      (node (ref "IC301") (pin "10") (pinfunction "A2_10") (pintype "input"))
      (node (ref "IC302") (pin "10") (pinfunction "A2_10") (pintype "input"))
      (node (ref "IC303") (pin "10") (pinfunction "A2_10") (pintype "input"))
      (node (ref "IC304") (pin "10") (pinfunction "A2_10") (pintype "input"))
      (node (ref "IC305") (pin "10") (pinfunction "A2_10") (pintype "input"))
      (node (ref "IC306") (pin "10") (pinfunction "A2_10") (pintype "input"))
      (node (ref "IC307") (pin "10") (pinfunction "A2_10") (pintype "input"))
      (node (ref "IC308") (pin "10") (pinfunction "A2_10") (pintype "input"))
    )
    (net (code "59") (name "RAM_A3") (class "Default")
      (node (ref "IC103") (pin "15") (pinfunction "B4_15") (pintype "bidirectional"))
      (node (ref "IC201") (pin "9") (pinfunction "A3_9") (pintype "input"))
      (node (ref "IC202") (pin "9") (pinfunction "A3_9") (pintype "input"))
      (node (ref "IC203") (pin "9") (pinfunction "A3_9") (pintype "input"))
      (node (ref "IC204") (pin "9") (pinfunction "A3_9") (pintype "input"))
      (node (ref "IC205") (pin "9") (pinfunction "A3_9") (pintype "input"))
      (node (ref "IC206") (pin "9") (pinfunction "A3_9") (pintype "input"))
      (node (ref "IC207") (pin "9") (pinfunction "A3_9") (pintype "input"))
      (node (ref "IC208") (pin "9") (pinfunction "A3_9") (pintype "input"))
      (node (ref "IC301") (pin "9") (pinfunction "A3_9") (pintype "input"))
      (node (ref "IC302") (pin "9") (pinfunction "A3_9") (pintype "input"))
      (node (ref "IC303") (pin "9") (pinfunction "A3_9") (pintype "input"))
      (node (ref "IC304") (pin "9") (pinfunction "A3_9") (pintype "input"))
      (node (ref "IC305") (pin "9") (pinfunction "A3_9") (pintype "input"))
      (node (ref "IC306") (pin "9") (pinfunction "A3_9") (pintype "input"))
      (node (ref "IC307") (pin "9") (pinfunction "A3_9") (pintype "input"))
      (node (ref "IC308") (pin "9") (pinfunction "A3_9") (pintype "input"))
    )
    (net (code "60") (name "RAM_A4") (class "Default")
      (node (ref "IC103") (pin "14") (pinfunction "B5_14") (pintype "bidirectional"))
      (node (ref "IC201") (pin "8") (pinfunction "A4_8") (pintype "input"))
      (node (ref "IC202") (pin "8") (pinfunction "A4_8") (pintype "input"))
      (node (ref "IC203") (pin "8") (pinfunction "A4_8") (pintype "input"))
      (node (ref "IC204") (pin "8") (pinfunction "A4_8") (pintype "input"))
      (node (ref "IC205") (pin "8") (pinfunction "A4_8") (pintype "input"))
      (node (ref "IC206") (pin "8") (pinfunction "A4_8") (pintype "input"))
      (node (ref "IC207") (pin "8") (pinfunction "A4_8") (pintype "input"))
      (node (ref "IC208") (pin "8") (pinfunction "A4_8") (pintype "input"))
      (node (ref "IC301") (pin "8") (pinfunction "A4_8") (pintype "input"))
      (node (ref "IC302") (pin "8") (pinfunction "A4_8") (pintype "input"))
      (node (ref "IC303") (pin "8") (pinfunction "A4_8") (pintype "input"))
      (node (ref "IC304") (pin "8") (pinfunction "A4_8") (pintype "input"))
      (node (ref "IC305") (pin "8") (pinfunction "A4_8") (pintype "input"))
      (node (ref "IC306") (pin "8") (pinfunction "A4_8") (pintype "input"))
      (node (ref "IC307") (pin "8") (pinfunction "A4_8") (pintype "input"))
      (node (ref "IC308") (pin "8") (pinfunction "A4_8") (pintype "input"))
    )
    (net (code "61") (name "RAM_A5") (class "Default")
      (node (ref "IC103") (pin "13") (pinfunction "B6_13") (pintype "bidirectional"))
      (node (ref "IC201") (pin "7") (pinfunction "A5_7") (pintype "input"))
      (node (ref "IC202") (pin "7") (pinfunction "A5_7") (pintype "input"))
      (node (ref "IC203") (pin "7") (pinfunction "A5_7") (pintype "input"))
      (node (ref "IC204") (pin "7") (pinfunction "A5_7") (pintype "input"))
      (node (ref "IC205") (pin "7") (pinfunction "A5_7") (pintype "input"))
      (node (ref "IC206") (pin "7") (pinfunction "A5_7") (pintype "input"))
      (node (ref "IC207") (pin "7") (pinfunction "A5_7") (pintype "input"))
      (node (ref "IC208") (pin "7") (pinfunction "A5_7") (pintype "input"))
      (node (ref "IC301") (pin "7") (pinfunction "A5_7") (pintype "input"))
      (node (ref "IC302") (pin "7") (pinfunction "A5_7") (pintype "input"))
      (node (ref "IC303") (pin "7") (pinfunction "A5_7") (pintype "input"))
      (node (ref "IC304") (pin "7") (pinfunction "A5_7") (pintype "input"))
      (node (ref "IC305") (pin "7") (pinfunction "A5_7") (pintype "input"))
      (node (ref "IC306") (pin "7") (pinfunction "A5_7") (pintype "input"))
      (node (ref "IC307") (pin "7") (pinfunction "A5_7") (pintype "input"))
      (node (ref "IC308") (pin "7") (pinfunction "A5_7") (pintype "input"))
    )
    (net (code "62") (name "RAM_A6") (class "Default")
      (node (ref "IC103") (pin "12") (pinfunction "B7_12") (pintype "bidirectional"))
      (node (ref "IC201") (pin "6") (pinfunction "A6_6") (pintype "input"))
      (node (ref "IC202") (pin "6") (pinfunction "A6_6") (pintype "input"))
      (node (ref "IC203") (pin "6") (pinfunction "A6_6") (pintype "input"))
      (node (ref "IC204") (pin "6") (pinfunction "A6_6") (pintype "input"))
      (node (ref "IC205") (pin "6") (pinfunction "A6_6") (pintype "input"))
      (node (ref "IC206") (pin "6") (pinfunction "A6_6") (pintype "input"))
      (node (ref "IC207") (pin "6") (pinfunction "A6_6") (pintype "input"))
      (node (ref "IC208") (pin "6") (pinfunction "A6_6") (pintype "input"))
      (node (ref "IC301") (pin "6") (pinfunction "A6_6") (pintype "input"))
      (node (ref "IC302") (pin "6") (pinfunction "A6_6") (pintype "input"))
      (node (ref "IC303") (pin "6") (pinfunction "A6_6") (pintype "input"))
      (node (ref "IC304") (pin "6") (pinfunction "A6_6") (pintype "input"))
      (node (ref "IC305") (pin "6") (pinfunction "A6_6") (pintype "input"))
      (node (ref "IC306") (pin "6") (pinfunction "A6_6") (pintype "input"))
      (node (ref "IC307") (pin "6") (pinfunction "A6_6") (pintype "input"))
      (node (ref "IC308") (pin "6") (pinfunction "A6_6") (pintype "input"))
    )
    (net (code "63") (name "RAM_A7") (class "Default")
      (node (ref "IC103") (pin "11") (pinfunction "B8_11") (pintype "bidirectional"))
      (node (ref "IC201") (pin "5") (pinfunction "A7_5") (pintype "input"))
      (node (ref "IC202") (pin "5") (pinfunction "A7_5") (pintype "input"))
      (node (ref "IC203") (pin "5") (pinfunction "A7_5") (pintype "input"))
      (node (ref "IC204") (pin "5") (pinfunction "A7_5") (pintype "input"))
      (node (ref "IC205") (pin "5") (pinfunction "A7_5") (pintype "input"))
      (node (ref "IC206") (pin "5") (pinfunction "A7_5") (pintype "input"))
      (node (ref "IC207") (pin "5") (pinfunction "A7_5") (pintype "input"))
      (node (ref "IC208") (pin "5") (pinfunction "A7_5") (pintype "input"))
      (node (ref "IC301") (pin "5") (pinfunction "A7_5") (pintype "input"))
      (node (ref "IC302") (pin "5") (pinfunction "A7_5") (pintype "input"))
      (node (ref "IC303") (pin "5") (pinfunction "A7_5") (pintype "input"))
      (node (ref "IC304") (pin "5") (pinfunction "A7_5") (pintype "input"))
      (node (ref "IC305") (pin "5") (pinfunction "A7_5") (pintype "input"))
      (node (ref "IC306") (pin "5") (pinfunction "A7_5") (pintype "input"))
      (node (ref "IC307") (pin "5") (pinfunction "A7_5") (pintype "input"))
      (node (ref "IC308") (pin "5") (pinfunction "A7_5") (pintype "input"))
    )
    (net (code "64") (name "RAM_A8") (class "Default")
      (node (ref "IC104") (pin "18") (pinfunction "B1_18") (pintype "bidirectional"))
      (node (ref "IC201") (pin "27") (pinfunction "A8_27") (pintype "input"))
      (node (ref "IC202") (pin "27") (pinfunction "A8_27") (pintype "input"))
      (node (ref "IC203") (pin "27") (pinfunction "A8_27") (pintype "input"))
      (node (ref "IC204") (pin "27") (pinfunction "A8_27") (pintype "input"))
      (node (ref "IC205") (pin "27") (pinfunction "A8_27") (pintype "input"))
      (node (ref "IC206") (pin "27") (pinfunction "A8_27") (pintype "input"))
      (node (ref "IC207") (pin "27") (pinfunction "A8_27") (pintype "input"))
      (node (ref "IC208") (pin "27") (pinfunction "A8_27") (pintype "input"))
      (node (ref "IC301") (pin "27") (pinfunction "A8_27") (pintype "input"))
      (node (ref "IC302") (pin "27") (pinfunction "A8_27") (pintype "input"))
      (node (ref "IC303") (pin "27") (pinfunction "A8_27") (pintype "input"))
      (node (ref "IC304") (pin "27") (pinfunction "A8_27") (pintype "input"))
      (node (ref "IC305") (pin "27") (pinfunction "A8_27") (pintype "input"))
      (node (ref "IC306") (pin "27") (pinfunction "A8_27") (pintype "input"))
      (node (ref "IC307") (pin "27") (pinfunction "A8_27") (pintype "input"))
      (node (ref "IC308") (pin "27") (pinfunction "A8_27") (pintype "input"))
    )
    (net (code "65") (name "RAM_A9") (class "Default")
      (node (ref "IC104") (pin "17") (pinfunction "B2_17") (pintype "bidirectional"))
      (node (ref "IC201") (pin "26") (pinfunction "A9_26") (pintype "input"))
      (node (ref "IC202") (pin "26") (pinfunction "A9_26") (pintype "input"))
      (node (ref "IC203") (pin "26") (pinfunction "A9_26") (pintype "input"))
      (node (ref "IC204") (pin "26") (pinfunction "A9_26") (pintype "input"))
      (node (ref "IC205") (pin "26") (pinfunction "A9_26") (pintype "input"))
      (node (ref "IC206") (pin "26") (pinfunction "A9_26") (pintype "input"))
      (node (ref "IC207") (pin "26") (pinfunction "A9_26") (pintype "input"))
      (node (ref "IC208") (pin "26") (pinfunction "A9_26") (pintype "input"))
      (node (ref "IC301") (pin "26") (pinfunction "A9_26") (pintype "input"))
      (node (ref "IC302") (pin "26") (pinfunction "A9_26") (pintype "input"))
      (node (ref "IC303") (pin "26") (pinfunction "A9_26") (pintype "input"))
      (node (ref "IC304") (pin "26") (pinfunction "A9_26") (pintype "input"))
      (node (ref "IC305") (pin "26") (pinfunction "A9_26") (pintype "input"))
      (node (ref "IC306") (pin "26") (pinfunction "A9_26") (pintype "input"))
      (node (ref "IC307") (pin "26") (pinfunction "A9_26") (pintype "input"))
      (node (ref "IC308") (pin "26") (pinfunction "A9_26") (pintype "input"))
    )
    (net (code "66") (name "RAM_A10") (class "Default")
      (node (ref "IC104") (pin "16") (pinfunction "B3_16") (pintype "bidirectional"))
      (node (ref "IC201") (pin "23") (pinfunction "A10_23") (pintype "input"))
      (node (ref "IC202") (pin "23") (pinfunction "A10_23") (pintype "input"))
      (node (ref "IC203") (pin "23") (pinfunction "A10_23") (pintype "input"))
      (node (ref "IC204") (pin "23") (pinfunction "A10_23") (pintype "input"))
      (node (ref "IC205") (pin "23") (pinfunction "A10_23") (pintype "input"))
      (node (ref "IC206") (pin "23") (pinfunction "A10_23") (pintype "input"))
      (node (ref "IC207") (pin "23") (pinfunction "A10_23") (pintype "input"))
      (node (ref "IC208") (pin "23") (pinfunction "A10_23") (pintype "input"))
      (node (ref "IC301") (pin "23") (pinfunction "A10_23") (pintype "input"))
      (node (ref "IC302") (pin "23") (pinfunction "A10_23") (pintype "input"))
      (node (ref "IC303") (pin "23") (pinfunction "A10_23") (pintype "input"))
      (node (ref "IC304") (pin "23") (pinfunction "A10_23") (pintype "input"))
      (node (ref "IC305") (pin "23") (pinfunction "A10_23") (pintype "input"))
      (node (ref "IC306") (pin "23") (pinfunction "A10_23") (pintype "input"))
      (node (ref "IC307") (pin "23") (pinfunction "A10_23") (pintype "input"))
      (node (ref "IC308") (pin "23") (pinfunction "A10_23") (pintype "input"))
    )
    (net (code "67") (name "RAM_A11") (class "Default")
      (node (ref "IC104") (pin "15") (pinfunction "B4_15") (pintype "bidirectional"))
      (node (ref "IC201") (pin "25") (pinfunction "A11_25") (pintype "input"))
      (node (ref "IC202") (pin "25") (pinfunction "A11_25") (pintype "input"))
      (node (ref "IC203") (pin "25") (pinfunction "A11_25") (pintype "input"))
      (node (ref "IC204") (pin "25") (pinfunction "A11_25") (pintype "input"))
      (node (ref "IC205") (pin "25") (pinfunction "A11_25") (pintype "input"))
      (node (ref "IC206") (pin "25") (pinfunction "A11_25") (pintype "input"))
      (node (ref "IC207") (pin "25") (pinfunction "A11_25") (pintype "input"))
      (node (ref "IC208") (pin "25") (pinfunction "A11_25") (pintype "input"))
      (node (ref "IC301") (pin "25") (pinfunction "A11_25") (pintype "input"))
      (node (ref "IC302") (pin "25") (pinfunction "A11_25") (pintype "input"))
      (node (ref "IC303") (pin "25") (pinfunction "A11_25") (pintype "input"))
      (node (ref "IC304") (pin "25") (pinfunction "A11_25") (pintype "input"))
      (node (ref "IC305") (pin "25") (pinfunction "A11_25") (pintype "input"))
      (node (ref "IC306") (pin "25") (pinfunction "A11_25") (pintype "input"))
      (node (ref "IC307") (pin "25") (pinfunction "A11_25") (pintype "input"))
      (node (ref "IC308") (pin "25") (pinfunction "A11_25") (pintype "input"))
    )
    (net (code "68") (name "RAM_A12") (class "Default")
      (node (ref "IC104") (pin "14") (pinfunction "B5_14") (pintype "bidirectional"))
      (node (ref "IC201") (pin "4") (pinfunction "A12_4") (pintype "input"))
      (node (ref "IC202") (pin "4") (pinfunction "A12_4") (pintype "input"))
      (node (ref "IC203") (pin "4") (pinfunction "A12_4") (pintype "input"))
      (node (ref "IC204") (pin "4") (pinfunction "A12_4") (pintype "input"))
      (node (ref "IC205") (pin "4") (pinfunction "A12_4") (pintype "input"))
      (node (ref "IC206") (pin "4") (pinfunction "A12_4") (pintype "input"))
      (node (ref "IC207") (pin "4") (pinfunction "A12_4") (pintype "input"))
      (node (ref "IC208") (pin "4") (pinfunction "A12_4") (pintype "input"))
      (node (ref "IC301") (pin "4") (pinfunction "A12_4") (pintype "input"))
      (node (ref "IC302") (pin "4") (pinfunction "A12_4") (pintype "input"))
      (node (ref "IC303") (pin "4") (pinfunction "A12_4") (pintype "input"))
      (node (ref "IC304") (pin "4") (pinfunction "A12_4") (pintype "input"))
      (node (ref "IC305") (pin "4") (pinfunction "A12_4") (pintype "input"))
      (node (ref "IC306") (pin "4") (pinfunction "A12_4") (pintype "input"))
      (node (ref "IC307") (pin "4") (pinfunction "A12_4") (pintype "input"))
      (node (ref "IC308") (pin "4") (pinfunction "A12_4") (pintype "input"))
    )
    (net (code "69") (name "RAM_A13") (class "Default")
      (node (ref "IC104") (pin "13") (pinfunction "B6_13") (pintype "bidirectional"))
      (node (ref "IC201") (pin "28") (pinfunction "A13_28") (pintype "input"))
      (node (ref "IC202") (pin "28") (pinfunction "A13_28") (pintype "input"))
      (node (ref "IC203") (pin "28") (pinfunction "A13_28") (pintype "input"))
      (node (ref "IC204") (pin "28") (pinfunction "A13_28") (pintype "input"))
      (node (ref "IC205") (pin "28") (pinfunction "A13_28") (pintype "input"))
      (node (ref "IC206") (pin "28") (pinfunction "A13_28") (pintype "input"))
      (node (ref "IC207") (pin "28") (pinfunction "A13_28") (pintype "input"))
      (node (ref "IC208") (pin "28") (pinfunction "A13_28") (pintype "input"))
      (node (ref "IC301") (pin "28") (pinfunction "A13_28") (pintype "input"))
      (node (ref "IC302") (pin "28") (pinfunction "A13_28") (pintype "input"))
      (node (ref "IC303") (pin "28") (pinfunction "A13_28") (pintype "input"))
      (node (ref "IC304") (pin "28") (pinfunction "A13_28") (pintype "input"))
      (node (ref "IC305") (pin "28") (pinfunction "A13_28") (pintype "input"))
      (node (ref "IC306") (pin "28") (pinfunction "A13_28") (pintype "input"))
      (node (ref "IC307") (pin "28") (pinfunction "A13_28") (pintype "input"))
      (node (ref "IC308") (pin "28") (pinfunction "A13_28") (pintype "input"))
    )
    (net (code "70") (name "RAM_A14") (class "Default")
      (node (ref "IC104") (pin "12") (pinfunction "B7_12") (pintype "bidirectional"))
      (node (ref "IC201") (pin "3") (pinfunction "A14_3") (pintype "input"))
      (node (ref "IC202") (pin "3") (pinfunction "A14_3") (pintype "input"))
      (node (ref "IC203") (pin "3") (pinfunction "A14_3") (pintype "input"))
      (node (ref "IC204") (pin "3") (pinfunction "A14_3") (pintype "input"))
      (node (ref "IC205") (pin "3") (pinfunction "A14_3") (pintype "input"))
      (node (ref "IC206") (pin "3") (pinfunction "A14_3") (pintype "input"))
      (node (ref "IC207") (pin "3") (pinfunction "A14_3") (pintype "input"))
      (node (ref "IC208") (pin "3") (pinfunction "A14_3") (pintype "input"))
      (node (ref "IC301") (pin "3") (pinfunction "A14_3") (pintype "input"))
      (node (ref "IC302") (pin "3") (pinfunction "A14_3") (pintype "input"))
      (node (ref "IC303") (pin "3") (pinfunction "A14_3") (pintype "input"))
      (node (ref "IC304") (pin "3") (pinfunction "A14_3") (pintype "input"))
      (node (ref "IC305") (pin "3") (pinfunction "A14_3") (pintype "input"))
      (node (ref "IC306") (pin "3") (pinfunction "A14_3") (pintype "input"))
      (node (ref "IC307") (pin "3") (pinfunction "A14_3") (pintype "input"))
      (node (ref "IC308") (pin "3") (pinfunction "A14_3") (pintype "input"))
    )
    (net (code "71") (name "RAM_A15") (class "Default")
      (node (ref "IC104") (pin "11") (pinfunction "B8_11") (pintype "bidirectional"))
      (node (ref "IC201") (pin "31") (pinfunction "A15_31") (pintype "input"))
      (node (ref "IC202") (pin "31") (pinfunction "A15_31") (pintype "input"))
      (node (ref "IC203") (pin "31") (pinfunction "A15_31") (pintype "input"))
      (node (ref "IC204") (pin "31") (pinfunction "A15_31") (pintype "input"))
      (node (ref "IC205") (pin "31") (pinfunction "A15_31") (pintype "input"))
      (node (ref "IC206") (pin "31") (pinfunction "A15_31") (pintype "input"))
      (node (ref "IC207") (pin "31") (pinfunction "A15_31") (pintype "input"))
      (node (ref "IC208") (pin "31") (pinfunction "A15_31") (pintype "input"))
      (node (ref "IC301") (pin "31") (pinfunction "A15_31") (pintype "input"))
      (node (ref "IC302") (pin "31") (pinfunction "A15_31") (pintype "input"))
      (node (ref "IC303") (pin "31") (pinfunction "A15_31") (pintype "input"))
      (node (ref "IC304") (pin "31") (pinfunction "A15_31") (pintype "input"))
      (node (ref "IC305") (pin "31") (pinfunction "A15_31") (pintype "input"))
      (node (ref "IC306") (pin "31") (pinfunction "A15_31") (pintype "input"))
      (node (ref "IC307") (pin "31") (pinfunction "A15_31") (pintype "input"))
      (node (ref "IC308") (pin "31") (pinfunction "A15_31") (pintype "input"))
    )
    (net (code "72") (name "RAM_A16") (class "Default")
      (node (ref "IC105") (pin "11") (pinfunction "B1_11") (pintype "bidirectional"))
      (node (ref "IC201") (pin "2") (pinfunction "A16_2") (pintype "input"))
      (node (ref "IC202") (pin "2") (pinfunction "A16_2") (pintype "input"))
      (node (ref "IC203") (pin "2") (pinfunction "A16_2") (pintype "input"))
      (node (ref "IC204") (pin "2") (pinfunction "A16_2") (pintype "input"))
      (node (ref "IC205") (pin "2") (pinfunction "A16_2") (pintype "input"))
      (node (ref "IC206") (pin "2") (pinfunction "A16_2") (pintype "input"))
      (node (ref "IC207") (pin "2") (pinfunction "A16_2") (pintype "input"))
      (node (ref "IC208") (pin "2") (pinfunction "A16_2") (pintype "input"))
      (node (ref "IC301") (pin "2") (pinfunction "A16_2") (pintype "input"))
      (node (ref "IC302") (pin "2") (pinfunction "A16_2") (pintype "input"))
      (node (ref "IC303") (pin "2") (pinfunction "A16_2") (pintype "input"))
      (node (ref "IC304") (pin "2") (pinfunction "A16_2") (pintype "input"))
      (node (ref "IC305") (pin "2") (pinfunction "A16_2") (pintype "input"))
      (node (ref "IC306") (pin "2") (pinfunction "A16_2") (pintype "input"))
      (node (ref "IC307") (pin "2") (pinfunction "A16_2") (pintype "input"))
      (node (ref "IC308") (pin "2") (pinfunction "A16_2") (pintype "input"))
    )
    (net (code "73") (name "RAM_D0") (class "Default")
      (node (ref "IC101") (pin "18") (pinfunction "B1_18") (pintype "bidirectional"))
      (node (ref "IC201") (pin "13") (pinfunction "D0_13") (pintype "bidirectional"))
      (node (ref "IC202") (pin "13") (pinfunction "D0_13") (pintype "bidirectional"))
      (node (ref "IC203") (pin "13") (pinfunction "D0_13") (pintype "bidirectional"))
      (node (ref "IC204") (pin "13") (pinfunction "D0_13") (pintype "bidirectional"))
      (node (ref "IC205") (pin "13") (pinfunction "D0_13") (pintype "bidirectional"))
      (node (ref "IC206") (pin "13") (pinfunction "D0_13") (pintype "bidirectional"))
      (node (ref "IC207") (pin "13") (pinfunction "D0_13") (pintype "bidirectional"))
      (node (ref "IC208") (pin "13") (pinfunction "D0_13") (pintype "bidirectional"))
    )
    (net (code "74") (name "RAM_D1") (class "Default")
      (node (ref "IC101") (pin "17") (pinfunction "B2_17") (pintype "bidirectional"))
      (node (ref "IC201") (pin "14") (pinfunction "D1_14") (pintype "bidirectional"))
      (node (ref "IC202") (pin "14") (pinfunction "D1_14") (pintype "bidirectional"))
      (node (ref "IC203") (pin "14") (pinfunction "D1_14") (pintype "bidirectional"))
      (node (ref "IC204") (pin "14") (pinfunction "D1_14") (pintype "bidirectional"))
      (node (ref "IC205") (pin "14") (pinfunction "D1_14") (pintype "bidirectional"))
      (node (ref "IC206") (pin "14") (pinfunction "D1_14") (pintype "bidirectional"))
      (node (ref "IC207") (pin "14") (pinfunction "D1_14") (pintype "bidirectional"))
      (node (ref "IC208") (pin "14") (pinfunction "D1_14") (pintype "bidirectional"))
    )
    (net (code "75") (name "RAM_D2") (class "Default")
      (node (ref "IC101") (pin "16") (pinfunction "B3_16") (pintype "bidirectional"))
      (node (ref "IC201") (pin "15") (pinfunction "D2_15") (pintype "bidirectional"))
      (node (ref "IC202") (pin "15") (pinfunction "D2_15") (pintype "bidirectional"))
      (node (ref "IC203") (pin "15") (pinfunction "D2_15") (pintype "bidirectional"))
      (node (ref "IC204") (pin "15") (pinfunction "D2_15") (pintype "bidirectional"))
      (node (ref "IC205") (pin "15") (pinfunction "D2_15") (pintype "bidirectional"))
      (node (ref "IC206") (pin "15") (pinfunction "D2_15") (pintype "bidirectional"))
      (node (ref "IC207") (pin "15") (pinfunction "D2_15") (pintype "bidirectional"))
      (node (ref "IC208") (pin "15") (pinfunction "D2_15") (pintype "bidirectional"))
    )
    (net (code "76") (name "RAM_D3") (class "Default")
      (node (ref "IC101") (pin "15") (pinfunction "B4_15") (pintype "bidirectional"))
      (node (ref "IC201") (pin "17") (pinfunction "D3_17") (pintype "bidirectional"))
      (node (ref "IC202") (pin "17") (pinfunction "D3_17") (pintype "bidirectional"))
      (node (ref "IC203") (pin "17") (pinfunction "D3_17") (pintype "bidirectional"))
      (node (ref "IC204") (pin "17") (pinfunction "D3_17") (pintype "bidirectional"))
      (node (ref "IC205") (pin "17") (pinfunction "D3_17") (pintype "bidirectional"))
      (node (ref "IC206") (pin "17") (pinfunction "D3_17") (pintype "bidirectional"))
      (node (ref "IC207") (pin "17") (pinfunction "D3_17") (pintype "bidirectional"))
      (node (ref "IC208") (pin "17") (pinfunction "D3_17") (pintype "bidirectional"))
    )
    (net (code "77") (name "RAM_D4") (class "Default")
      (node (ref "IC101") (pin "14") (pinfunction "B5_14") (pintype "bidirectional"))
      (node (ref "IC201") (pin "18") (pinfunction "D4_18") (pintype "bidirectional"))
      (node (ref "IC202") (pin "18") (pinfunction "D4_18") (pintype "bidirectional"))
      (node (ref "IC203") (pin "18") (pinfunction "D4_18") (pintype "bidirectional"))
      (node (ref "IC204") (pin "18") (pinfunction "D4_18") (pintype "bidirectional"))
      (node (ref "IC205") (pin "18") (pinfunction "D4_18") (pintype "bidirectional"))
      (node (ref "IC206") (pin "18") (pinfunction "D4_18") (pintype "bidirectional"))
      (node (ref "IC207") (pin "18") (pinfunction "D4_18") (pintype "bidirectional"))
      (node (ref "IC208") (pin "18") (pinfunction "D4_18") (pintype "bidirectional"))
    )
    (net (code "78") (name "RAM_D5") (class "Default")
      (node (ref "IC101") (pin "13") (pinfunction "B6_13") (pintype "bidirectional"))
      (node (ref "IC201") (pin "19") (pinfunction "D5_19") (pintype "bidirectional"))
      (node (ref "IC202") (pin "19") (pinfunction "D5_19") (pintype "bidirectional"))
      (node (ref "IC203") (pin "19") (pinfunction "D5_19") (pintype "bidirectional"))
      (node (ref "IC204") (pin "19") (pinfunction "D5_19") (pintype "bidirectional"))
      (node (ref "IC205") (pin "19") (pinfunction "D5_19") (pintype "bidirectional"))
      (node (ref "IC206") (pin "19") (pinfunction "D5_19") (pintype "bidirectional"))
      (node (ref "IC207") (pin "19") (pinfunction "D5_19") (pintype "bidirectional"))
      (node (ref "IC208") (pin "19") (pinfunction "D5_19") (pintype "bidirectional"))
    )
    (net (code "79") (name "RAM_D6") (class "Default")
      (node (ref "IC101") (pin "12") (pinfunction "B7_12") (pintype "bidirectional"))
      (node (ref "IC201") (pin "20") (pinfunction "D6_20") (pintype "bidirectional"))
      (node (ref "IC202") (pin "20") (pinfunction "D6_20") (pintype "bidirectional"))
      (node (ref "IC203") (pin "20") (pinfunction "D6_20") (pintype "bidirectional"))
      (node (ref "IC204") (pin "20") (pinfunction "D6_20") (pintype "bidirectional"))
      (node (ref "IC205") (pin "20") (pinfunction "D6_20") (pintype "bidirectional"))
      (node (ref "IC206") (pin "20") (pinfunction "D6_20") (pintype "bidirectional"))
      (node (ref "IC207") (pin "20") (pinfunction "D6_20") (pintype "bidirectional"))
      (node (ref "IC208") (pin "20") (pinfunction "D6_20") (pintype "bidirectional"))
    )
    (net (code "80") (name "RAM_D7") (class "Default")
      (node (ref "IC101") (pin "11") (pinfunction "B8_11") (pintype "bidirectional"))
      (node (ref "IC201") (pin "21") (pinfunction "D7_21") (pintype "bidirectional"))
      (node (ref "IC202") (pin "21") (pinfunction "D7_21") (pintype "bidirectional"))
      (node (ref "IC203") (pin "21") (pinfunction "D7_21") (pintype "bidirectional"))
      (node (ref "IC204") (pin "21") (pinfunction "D7_21") (pintype "bidirectional"))
      (node (ref "IC205") (pin "21") (pinfunction "D7_21") (pintype "bidirectional"))
      (node (ref "IC206") (pin "21") (pinfunction "D7_21") (pintype "bidirectional"))
      (node (ref "IC207") (pin "21") (pinfunction "D7_21") (pintype "bidirectional"))
      (node (ref "IC208") (pin "21") (pinfunction "D7_21") (pintype "bidirectional"))
    )
    (net (code "81") (name "RAM_D8") (class "Default")
      (node (ref "IC102") (pin "18") (pinfunction "B1_18") (pintype "bidirectional"))
      (node (ref "IC301") (pin "13") (pinfunction "D0_13") (pintype "bidirectional"))
      (node (ref "IC302") (pin "13") (pinfunction "D0_13") (pintype "bidirectional"))
      (node (ref "IC303") (pin "13") (pinfunction "D0_13") (pintype "bidirectional"))
      (node (ref "IC304") (pin "13") (pinfunction "D0_13") (pintype "bidirectional"))
      (node (ref "IC305") (pin "13") (pinfunction "D0_13") (pintype "bidirectional"))
      (node (ref "IC306") (pin "13") (pinfunction "D0_13") (pintype "bidirectional"))
      (node (ref "IC307") (pin "13") (pinfunction "D0_13") (pintype "bidirectional"))
      (node (ref "IC308") (pin "13") (pinfunction "D0_13") (pintype "bidirectional"))
    )
    (net (code "82") (name "RAM_D9") (class "Default")
      (node (ref "IC102") (pin "17") (pinfunction "B2_17") (pintype "bidirectional"))
      (node (ref "IC301") (pin "14") (pinfunction "D1_14") (pintype "bidirectional"))
      (node (ref "IC302") (pin "14") (pinfunction "D1_14") (pintype "bidirectional"))
      (node (ref "IC303") (pin "14") (pinfunction "D1_14") (pintype "bidirectional"))
      (node (ref "IC304") (pin "14") (pinfunction "D1_14") (pintype "bidirectional"))
      (node (ref "IC305") (pin "14") (pinfunction "D1_14") (pintype "bidirectional"))
      (node (ref "IC306") (pin "14") (pinfunction "D1_14") (pintype "bidirectional"))
      (node (ref "IC307") (pin "14") (pinfunction "D1_14") (pintype "bidirectional"))
      (node (ref "IC308") (pin "14") (pinfunction "D1_14") (pintype "bidirectional"))
    )
    (net (code "83") (name "RAM_D10") (class "Default")
      (node (ref "IC102") (pin "16") (pinfunction "B3_16") (pintype "bidirectional"))
      (node (ref "IC301") (pin "15") (pinfunction "D2_15") (pintype "bidirectional"))
      (node (ref "IC302") (pin "15") (pinfunction "D2_15") (pintype "bidirectional"))
      (node (ref "IC303") (pin "15") (pinfunction "D2_15") (pintype "bidirectional"))
      (node (ref "IC304") (pin "15") (pinfunction "D2_15") (pintype "bidirectional"))
      (node (ref "IC305") (pin "15") (pinfunction "D2_15") (pintype "bidirectional"))
      (node (ref "IC306") (pin "15") (pinfunction "D2_15") (pintype "bidirectional"))
      (node (ref "IC307") (pin "15") (pinfunction "D2_15") (pintype "bidirectional"))
      (node (ref "IC308") (pin "15") (pinfunction "D2_15") (pintype "bidirectional"))
    )
    (net (code "84") (name "RAM_D11") (class "Default")
      (node (ref "IC102") (pin "15") (pinfunction "B4_15") (pintype "bidirectional"))
      (node (ref "IC301") (pin "17") (pinfunction "D3_17") (pintype "bidirectional"))
      (node (ref "IC302") (pin "17") (pinfunction "D3_17") (pintype "bidirectional"))
      (node (ref "IC303") (pin "17") (pinfunction "D3_17") (pintype "bidirectional"))
      (node (ref "IC304") (pin "17") (pinfunction "D3_17") (pintype "bidirectional"))
      (node (ref "IC305") (pin "17") (pinfunction "D3_17") (pintype "bidirectional"))
      (node (ref "IC306") (pin "17") (pinfunction "D3_17") (pintype "bidirectional"))
      (node (ref "IC307") (pin "17") (pinfunction "D3_17") (pintype "bidirectional"))
      (node (ref "IC308") (pin "17") (pinfunction "D3_17") (pintype "bidirectional"))
    )
    (net (code "85") (name "RAM_D12") (class "Default")
      (node (ref "IC102") (pin "14") (pinfunction "B5_14") (pintype "bidirectional"))
      (node (ref "IC301") (pin "18") (pinfunction "D4_18") (pintype "bidirectional"))
      (node (ref "IC302") (pin "18") (pinfunction "D4_18") (pintype "bidirectional"))
      (node (ref "IC303") (pin "18") (pinfunction "D4_18") (pintype "bidirectional"))
      (node (ref "IC304") (pin "18") (pinfunction "D4_18") (pintype "bidirectional"))
      (node (ref "IC305") (pin "18") (pinfunction "D4_18") (pintype "bidirectional"))
      (node (ref "IC306") (pin "18") (pinfunction "D4_18") (pintype "bidirectional"))
      (node (ref "IC307") (pin "18") (pinfunction "D4_18") (pintype "bidirectional"))
      (node (ref "IC308") (pin "18") (pinfunction "D4_18") (pintype "bidirectional"))
    )
    (net (code "86") (name "RAM_D13") (class "Default")
      (node (ref "IC102") (pin "13") (pinfunction "B6_13") (pintype "bidirectional"))
      (node (ref "IC301") (pin "19") (pinfunction "D5_19") (pintype "bidirectional"))
      (node (ref "IC302") (pin "19") (pinfunction "D5_19") (pintype "bidirectional"))
      (node (ref "IC303") (pin "19") (pinfunction "D5_19") (pintype "bidirectional"))
      (node (ref "IC304") (pin "19") (pinfunction "D5_19") (pintype "bidirectional"))
      (node (ref "IC305") (pin "19") (pinfunction "D5_19") (pintype "bidirectional"))
      (node (ref "IC306") (pin "19") (pinfunction "D5_19") (pintype "bidirectional"))
      (node (ref "IC307") (pin "19") (pinfunction "D5_19") (pintype "bidirectional"))
      (node (ref "IC308") (pin "19") (pinfunction "D5_19") (pintype "bidirectional"))
    )
    (net (code "87") (name "RAM_D14") (class "Default")
      (node (ref "IC102") (pin "12") (pinfunction "B7_12") (pintype "bidirectional"))
      (node (ref "IC301") (pin "20") (pinfunction "D6_20") (pintype "bidirectional"))
      (node (ref "IC302") (pin "20") (pinfunction "D6_20") (pintype "bidirectional"))
      (node (ref "IC303") (pin "20") (pinfunction "D6_20") (pintype "bidirectional"))
      (node (ref "IC304") (pin "20") (pinfunction "D6_20") (pintype "bidirectional"))
      (node (ref "IC305") (pin "20") (pinfunction "D6_20") (pintype "bidirectional"))
      (node (ref "IC306") (pin "20") (pinfunction "D6_20") (pintype "bidirectional"))
      (node (ref "IC307") (pin "20") (pinfunction "D6_20") (pintype "bidirectional"))
      (node (ref "IC308") (pin "20") (pinfunction "D6_20") (pintype "bidirectional"))
    )
    (net (code "88") (name "RAM_D15") (class "Default")
      (node (ref "IC102") (pin "11") (pinfunction "B8_11") (pintype "bidirectional"))
      (node (ref "IC301") (pin "21") (pinfunction "D7_21") (pintype "bidirectional"))
      (node (ref "IC302") (pin "21") (pinfunction "D7_21") (pintype "bidirectional"))
      (node (ref "IC303") (pin "21") (pinfunction "D7_21") (pintype "bidirectional"))
      (node (ref "IC304") (pin "21") (pinfunction "D7_21") (pintype "bidirectional"))
      (node (ref "IC305") (pin "21") (pinfunction "D7_21") (pintype "bidirectional"))
      (node (ref "IC306") (pin "21") (pinfunction "D7_21") (pintype "bidirectional"))
      (node (ref "IC307") (pin "21") (pinfunction "D7_21") (pintype "bidirectional"))
      (node (ref "IC308") (pin "21") (pinfunction "D7_21") (pintype "bidirectional"))
    )
    (net (code "89") (name "R{slash}~{W}") (class "Default")
      (node (ref "IC107") (pin "2") (pinfunction "IN2_2") (pintype "input"))
      (node (ref "SV101") (pin "12") (pinfunction "12_12") (pintype "passive"))
    )
    (net (code "90") (name "unconnected-(IC105A-B3-Pad9)") (class "Default")
      (node (ref "IC105") (pin "9") (pinfunction "B3_9") (pintype "bidirectional"))
    )
    (net (code "91") (name "unconnected-(IC105A-B4-Pad8)") (class "Default")
      (node (ref "IC105") (pin "8") (pinfunction "B4_8") (pintype "bidirectional"))
    )
    (net (code "92") (name "unconnected-(IC107-IO17-Pad17)") (class "Default")
      (node (ref "IC107") (pin "17") (pinfunction "IO17_17") (pintype "bidirectional"))
    )
    (net (code "93") (name "unconnected-(IC107-IO18-Pad18)") (class "Default")
      (node (ref "IC107") (pin "18") (pinfunction "IO18_18") (pintype "bidirectional"))
    )
    (net (code "94") (name "unconnected-(IC107-IO19-Pad19)") (class "Default")
      (node (ref "IC107") (pin "19") (pinfunction "IO19_19") (pintype "bidirectional"))
    )
    (net (code "95") (name "unconnected-(SV101-Pad5)") (class "Default")
      (node (ref "SV101") (pin "5") (pinfunction "5_5") (pintype "passive"))
    )
    (net (code "96") (name "unconnected-(SV101-Pad7)") (class "Default")
      (node (ref "SV101") (pin "7") (pinfunction "7_7") (pintype "passive"))
    )
    (net (code "97") (name "unconnected-(SV101-Pad8)") (class "Default")
      (node (ref "SV101") (pin "8") (pinfunction "8_8") (pintype "passive"))
    )
    (net (code "98") (name "unconnected-(SV101-Pad9)") (class "Default")
      (node (ref "SV101") (pin "9") (pinfunction "9_9") (pintype "passive"))
    )
    (net (code "99") (name "unconnected-(SV101-Pad15)") (class "Default")
      (node (ref "SV101") (pin "15") (pinfunction "15_15") (pintype "passive"))
    )
    (net (code "100") (name "unconnected-(SV101-Pad16)") (class "Default")
      (node (ref "SV101") (pin "16") (pinfunction "16_16") (pintype "passive"))
    )
    (net (code "101") (name "unconnected-(SV101-Pad41)") (class "Default")
      (node (ref "SV101") (pin "41") (pinfunction "41_41") (pintype "passive"))
    )
    (net (code "102") (name "unconnected-(SV101-Pad43)") (class "Default")
      (node (ref "SV101") (pin "43") (pinfunction "43_43") (pintype "passive"))
    )
    (net (code "103") (name "unconnected-(SV101-Pad44)") (class "Default")
      (node (ref "SV101") (pin "44") (pinfunction "44_44") (pintype "passive"))
    )
    (net (code "104") (name "~{AS}") (class "Default")
      (node (ref "IC107") (pin "5") (pinfunction "IN5_5") (pintype "input"))
      (node (ref "SV101") (pin "13") (pinfunction "13_13") (pintype "passive"))
    )
    (net (code "105") (name "~{CS_LED}") (class "Default")
      (node (ref "IC105") (pin "10") (pinfunction "B2_10") (pintype "bidirectional"))
      (node (ref "LED102") (pin "C") (pinfunction "C_C") (pintype "passive"))
    )
    (net (code "106") (name "~{CS}") (class "Default")
      (node (ref "IC101") (pin "19") (pinfunction "G_19") (pintype "input"))
      (node (ref "IC102") (pin "19") (pinfunction "G_19") (pintype "input"))
      (node (ref "IC105") (pin "4") (pinfunction "A2_4") (pintype "bidirectional"))
      (node (ref "IC106") (pin "4") (pinfunction "G2A_4") (pintype "input"))
      (node (ref "IC107") (pin "14") (pinfunction "IO14_14") (pintype "bidirectional"))
    )
    (net (code "107") (name "~{DTACK}") (class "Default")
      (node (ref "IC107") (pin "16") (pinfunction "IO16_16") (pintype "bidirectional"))
      (node (ref "SV101") (pin "10") (pinfunction "10_10") (pintype "passive"))
    )
    (net (code "108") (name "~{LDS}") (class "Default")
      (node (ref "IC107") (pin "3") (pinfunction "IN3_3") (pintype "input"))
      (node (ref "SV101") (pin "11") (pinfunction "11_11") (pintype "passive"))
    )
    (net (code "109") (name "~{LOE}") (class "Default")
      (node (ref "IC107") (pin "20") (pinfunction "IO20_20") (pintype "bidirectional"))
      (node (ref "IC201") (pin "24") (pinfunction "~{OE}_24") (pintype "input"))
      (node (ref "IC202") (pin "24") (pinfunction "~{OE}_24") (pintype "input"))
      (node (ref "IC203") (pin "24") (pinfunction "~{OE}_24") (pintype "input"))
      (node (ref "IC204") (pin "24") (pinfunction "~{OE}_24") (pintype "input"))
      (node (ref "IC205") (pin "24") (pinfunction "~{OE}_24") (pintype "input"))
      (node (ref "IC206") (pin "24") (pinfunction "~{OE}_24") (pintype "input"))
      (node (ref "IC207") (pin "24") (pinfunction "~{OE}_24") (pintype "input"))
      (node (ref "IC208") (pin "24") (pinfunction "~{OE}_24") (pintype "input"))
    )
    (net (code "110") (name "~{LWE}") (class "Default")
      (node (ref "IC107") (pin "21") (pinfunction "IO21_21") (pintype "bidirectional"))
      (node (ref "IC201") (pin "29") (pinfunction "~{WE}_29") (pintype "input"))
      (node (ref "IC202") (pin "29") (pinfunction "~{WE}_29") (pintype "input"))
      (node (ref "IC203") (pin "29") (pinfunction "~{WE}_29") (pintype "input"))
      (node (ref "IC204") (pin "29") (pinfunction "~{WE}_29") (pintype "input"))
      (node (ref "IC205") (pin "29") (pinfunction "~{WE}_29") (pintype "input"))
      (node (ref "IC206") (pin "29") (pinfunction "~{WE}_29") (pintype "input"))
      (node (ref "IC207") (pin "29") (pinfunction "~{WE}_29") (pintype "input"))
      (node (ref "IC208") (pin "29") (pinfunction "~{WE}_29") (pintype "input"))
    )
    (net (code "111") (name "~{RAM_CS0}") (class "Default")
      (node (ref "IC106") (pin "15") (pinfunction "Y0_15") (pintype "output"))
      (node (ref "IC201") (pin "22") (pinfunction "~{CE1}_22") (pintype "input"))
      (node (ref "IC301") (pin "22") (pinfunction "~{CE1}_22") (pintype "input"))
    )
    (net (code "112") (name "~{RAM_CS1}") (class "Default")
      (node (ref "IC106") (pin "14") (pinfunction "Y1_14") (pintype "output"))
      (node (ref "IC202") (pin "22") (pinfunction "~{CE1}_22") (pintype "input"))
      (node (ref "IC302") (pin "22") (pinfunction "~{CE1}_22") (pintype "input"))
    )
    (net (code "113") (name "~{RAM_CS2}") (class "Default")
      (node (ref "IC106") (pin "13") (pinfunction "Y2_13") (pintype "output"))
      (node (ref "IC203") (pin "22") (pinfunction "~{CE1}_22") (pintype "input"))
      (node (ref "IC303") (pin "22") (pinfunction "~{CE1}_22") (pintype "input"))
    )
    (net (code "114") (name "~{RAM_CS3}") (class "Default")
      (node (ref "IC106") (pin "12") (pinfunction "Y3_12") (pintype "output"))
      (node (ref "IC204") (pin "22") (pinfunction "~{CE1}_22") (pintype "input"))
      (node (ref "IC304") (pin "22") (pinfunction "~{CE1}_22") (pintype "input"))
    )
    (net (code "115") (name "~{RAM_CS4}") (class "Default")
      (node (ref "IC106") (pin "11") (pinfunction "Y4_11") (pintype "output"))
      (node (ref "IC205") (pin "22") (pinfunction "~{CE1}_22") (pintype "input"))
      (node (ref "IC305") (pin "22") (pinfunction "~{CE1}_22") (pintype "input"))
    )
    (net (code "116") (name "~{RAM_CS5}") (class "Default")
      (node (ref "IC106") (pin "10") (pinfunction "Y5_10") (pintype "output"))
      (node (ref "IC206") (pin "22") (pinfunction "~{CE1}_22") (pintype "input"))
      (node (ref "IC306") (pin "22") (pinfunction "~{CE1}_22") (pintype "input"))
    )
    (net (code "117") (name "~{RAM_CS6}") (class "Default")
      (node (ref "IC106") (pin "9") (pinfunction "Y6_9") (pintype "output"))
      (node (ref "IC207") (pin "22") (pinfunction "~{CE1}_22") (pintype "input"))
      (node (ref "IC307") (pin "22") (pinfunction "~{CE1}_22") (pintype "input"))
    )
    (net (code "118") (name "~{RAM_CS7}") (class "Default")
      (node (ref "IC106") (pin "7") (pinfunction "Y7_7") (pintype "output"))
      (node (ref "IC208") (pin "22") (pinfunction "~{CE1}_22") (pintype "input"))
      (node (ref "IC308") (pin "22") (pinfunction "~{CE1}_22") (pintype "input"))
    )
    (net (code "119") (name "~{RD}") (class "Default")
      (node (ref "IC101") (pin "1") (pinfunction "DIR_1") (pintype "input"))
      (node (ref "IC102") (pin "1") (pinfunction "DIR_1") (pintype "input"))
      (node (ref "IC107") (pin "15") (pinfunction "IO15_15") (pintype "bidirectional"))
    )
    (net (code "120") (name "~{RESET}") (class "Default")
      (node (ref "IC107") (pin "1") (pinfunction "IN1/CLK_1") (pintype "input"))
      (node (ref "SV101") (pin "6") (pinfunction "6_6") (pintype "passive"))
    )
    (net (code "121") (name "~{UDS}") (class "Default")
      (node (ref "IC107") (pin "4") (pinfunction "IN4_4") (pintype "input"))
      (node (ref "SV101") (pin "14") (pinfunction "14_14") (pintype "passive"))
    )
    (net (code "122") (name "~{UOE}") (class "Default")
      (node (ref "IC107") (pin "22") (pinfunction "IO22_22") (pintype "bidirectional"))
      (node (ref "IC301") (pin "24") (pinfunction "~{OE}_24") (pintype "input"))
      (node (ref "IC302") (pin "24") (pinfunction "~{OE}_24") (pintype "input"))
      (node (ref "IC303") (pin "24") (pinfunction "~{OE}_24") (pintype "input"))
      (node (ref "IC304") (pin "24") (pinfunction "~{OE}_24") (pintype "input"))
      (node (ref "IC305") (pin "24") (pinfunction "~{OE}_24") (pintype "input"))
      (node (ref "IC306") (pin "24") (pinfunction "~{OE}_24") (pintype "input"))
      (node (ref "IC307") (pin "24") (pinfunction "~{OE}_24") (pintype "input"))
      (node (ref "IC308") (pin "24") (pinfunction "~{OE}_24") (pintype "input"))
    )
    (net (code "123") (name "~{UWE}") (class "Default")
      (node (ref "IC107") (pin "23") (pinfunction "IO23_23") (pintype "bidirectional"))
      (node (ref "IC301") (pin "29") (pinfunction "~{WE}_29") (pintype "input"))
      (node (ref "IC302") (pin "29") (pinfunction "~{WE}_29") (pintype "input"))
      (node (ref "IC303") (pin "29") (pinfunction "~{WE}_29") (pintype "input"))
      (node (ref "IC304") (pin "29") (pinfunction "~{WE}_29") (pintype "input"))
      (node (ref "IC305") (pin "29") (pinfunction "~{WE}_29") (pintype "input"))
      (node (ref "IC306") (pin "29") (pinfunction "~{WE}_29") (pintype "input"))
      (node (ref "IC307") (pin "29") (pinfunction "~{WE}_29") (pintype "input"))
      (node (ref "IC308") (pin "29") (pinfunction "~{WE}_29") (pintype "input"))
    )
  )
)
